# Ali_Main_Board.net
KiCad netlist of a schematic drawn in Altium Designer
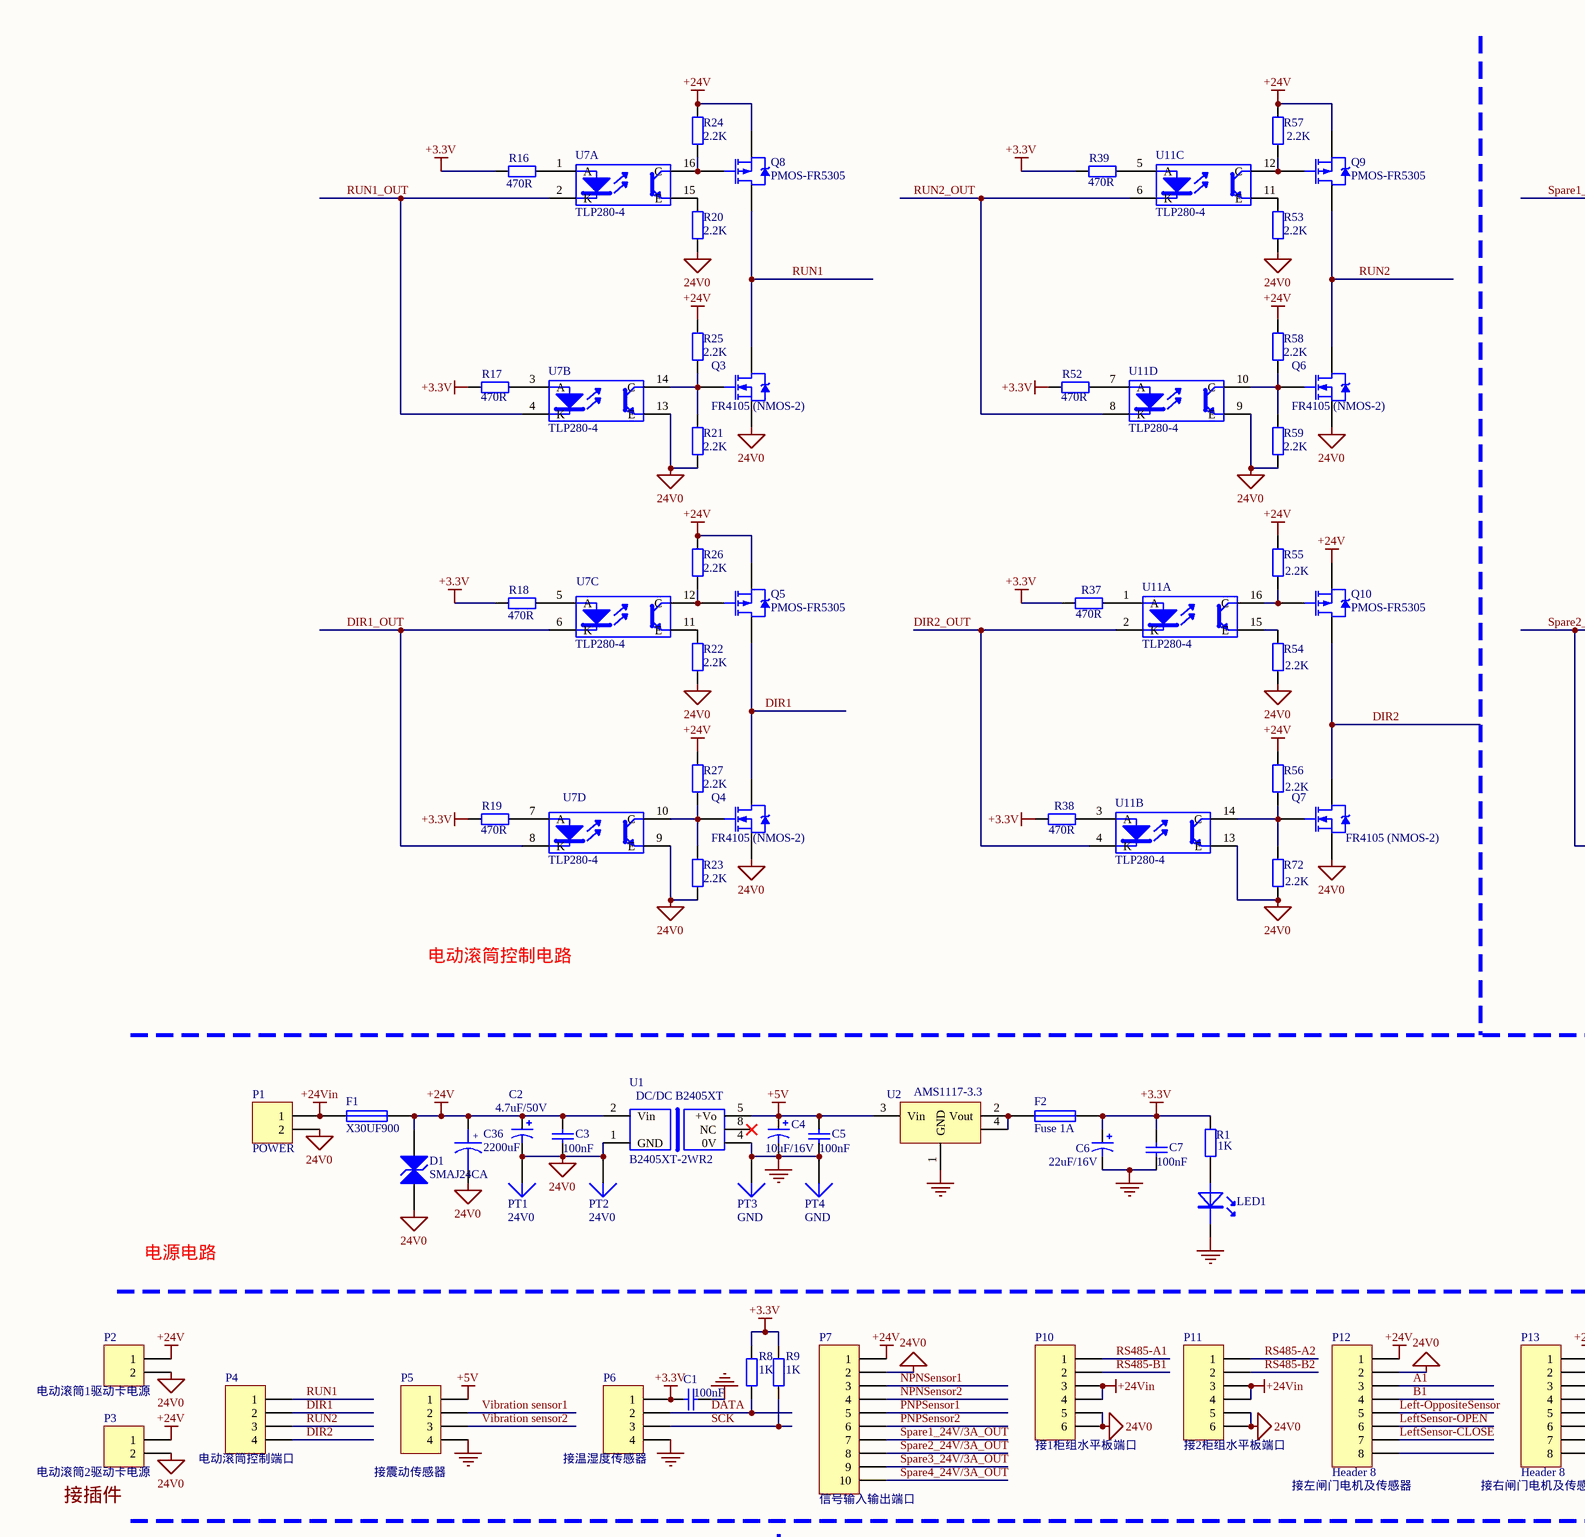
[diagram p0: Ali_Main_Board.SchDoc, top left]
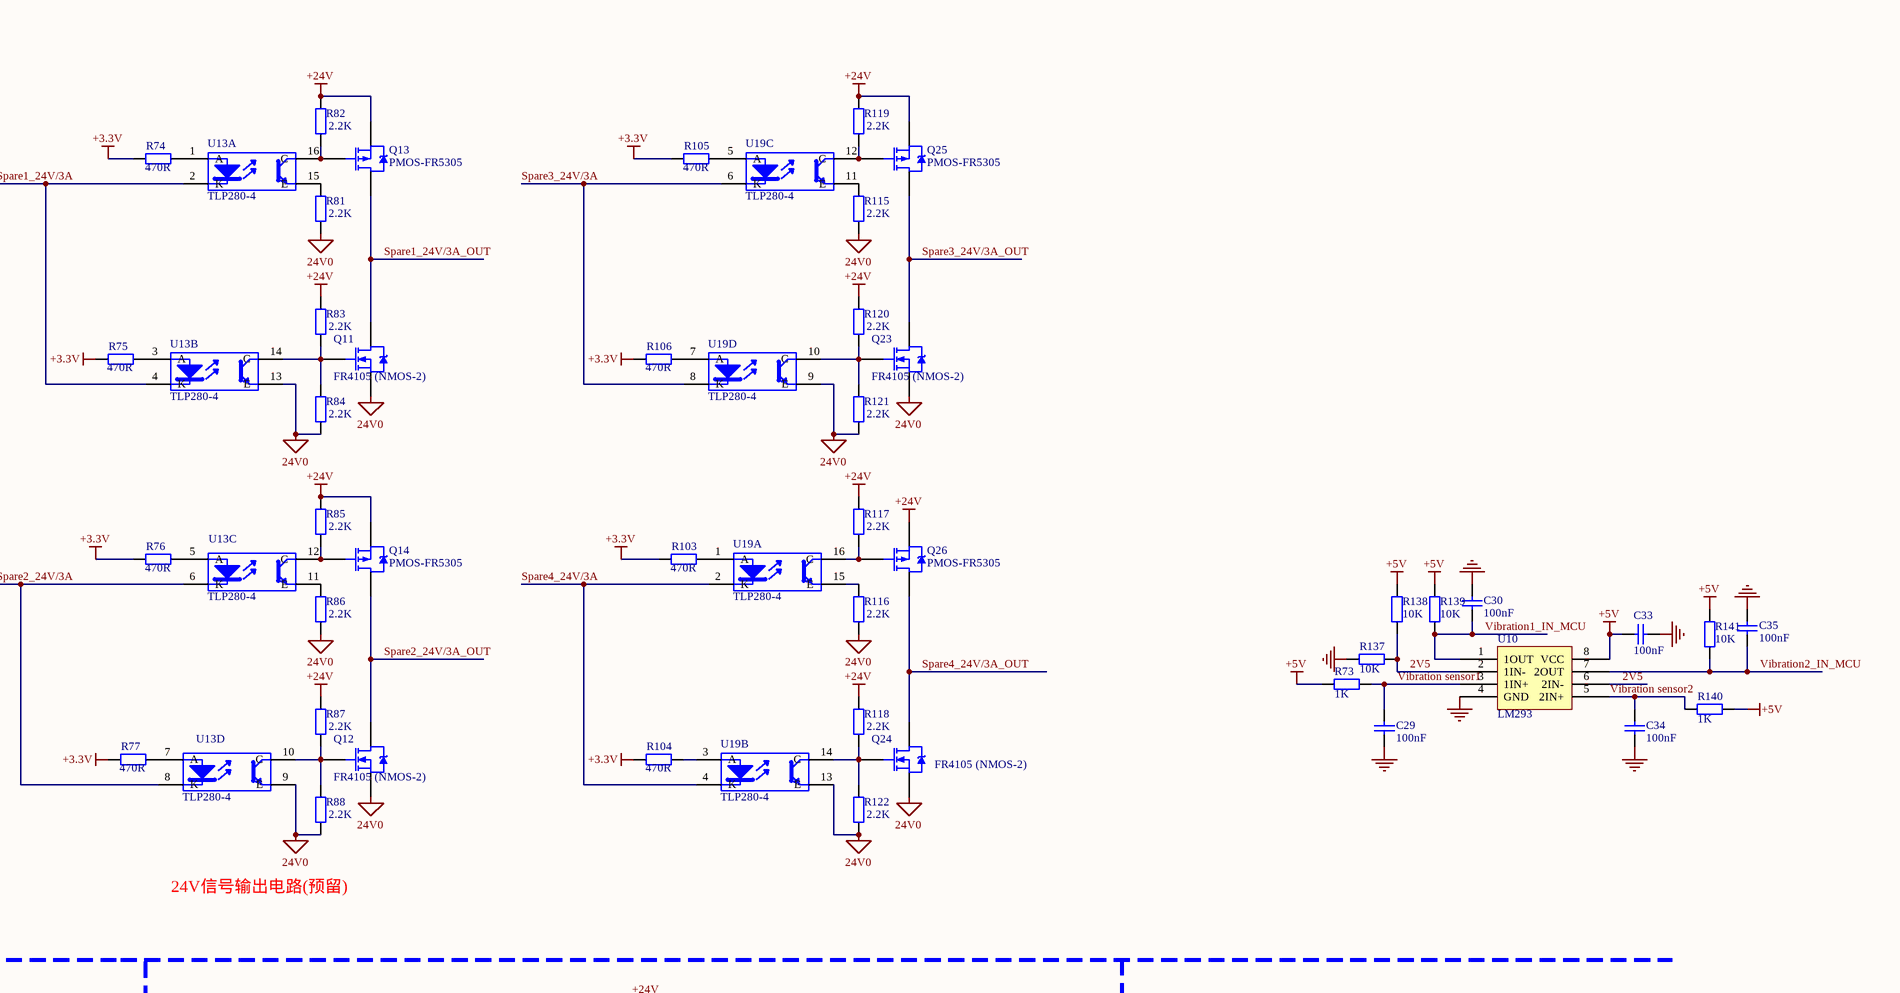
[diagram p1: Ali_Main_Board.SchDoc, top right]
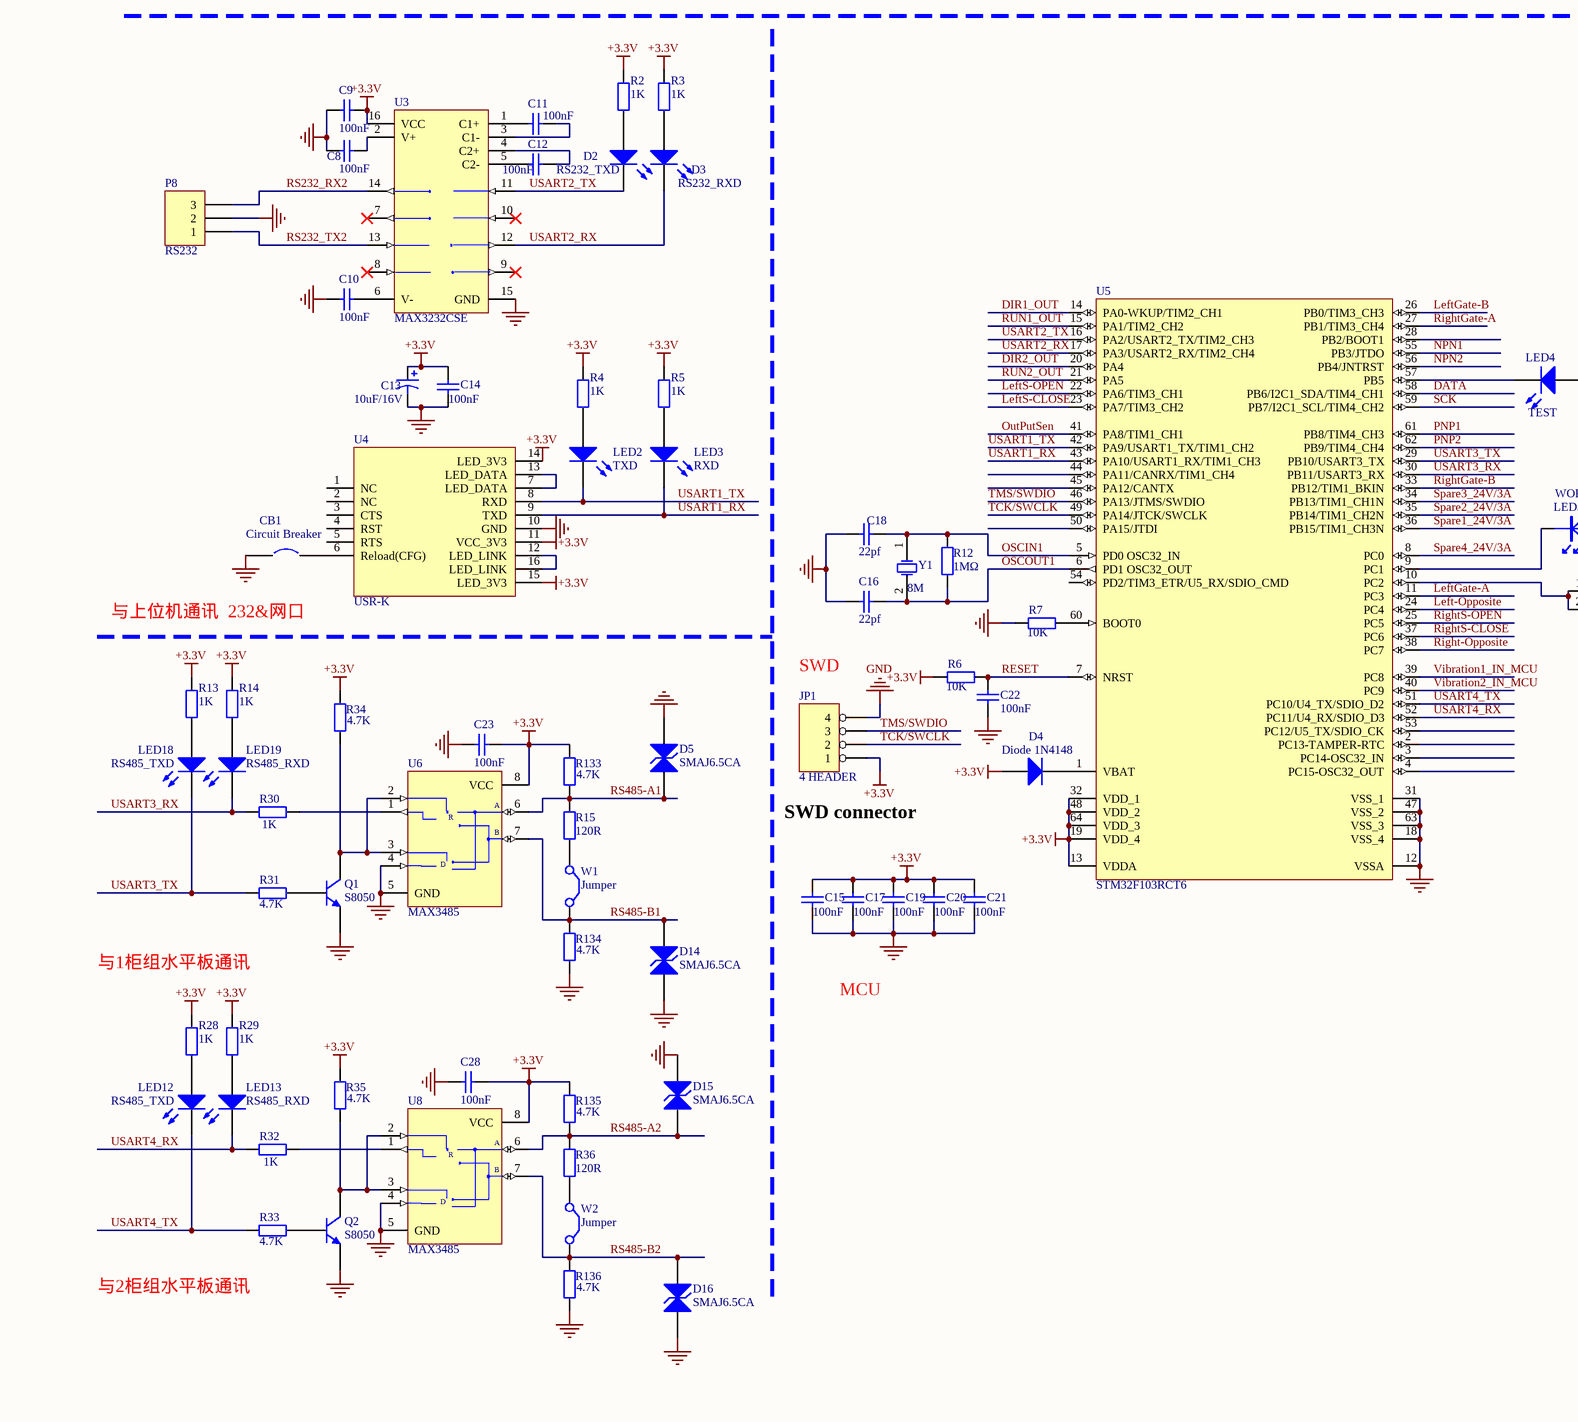
[diagram p2: Ali_Main_Board.SchDoc, bottom left]
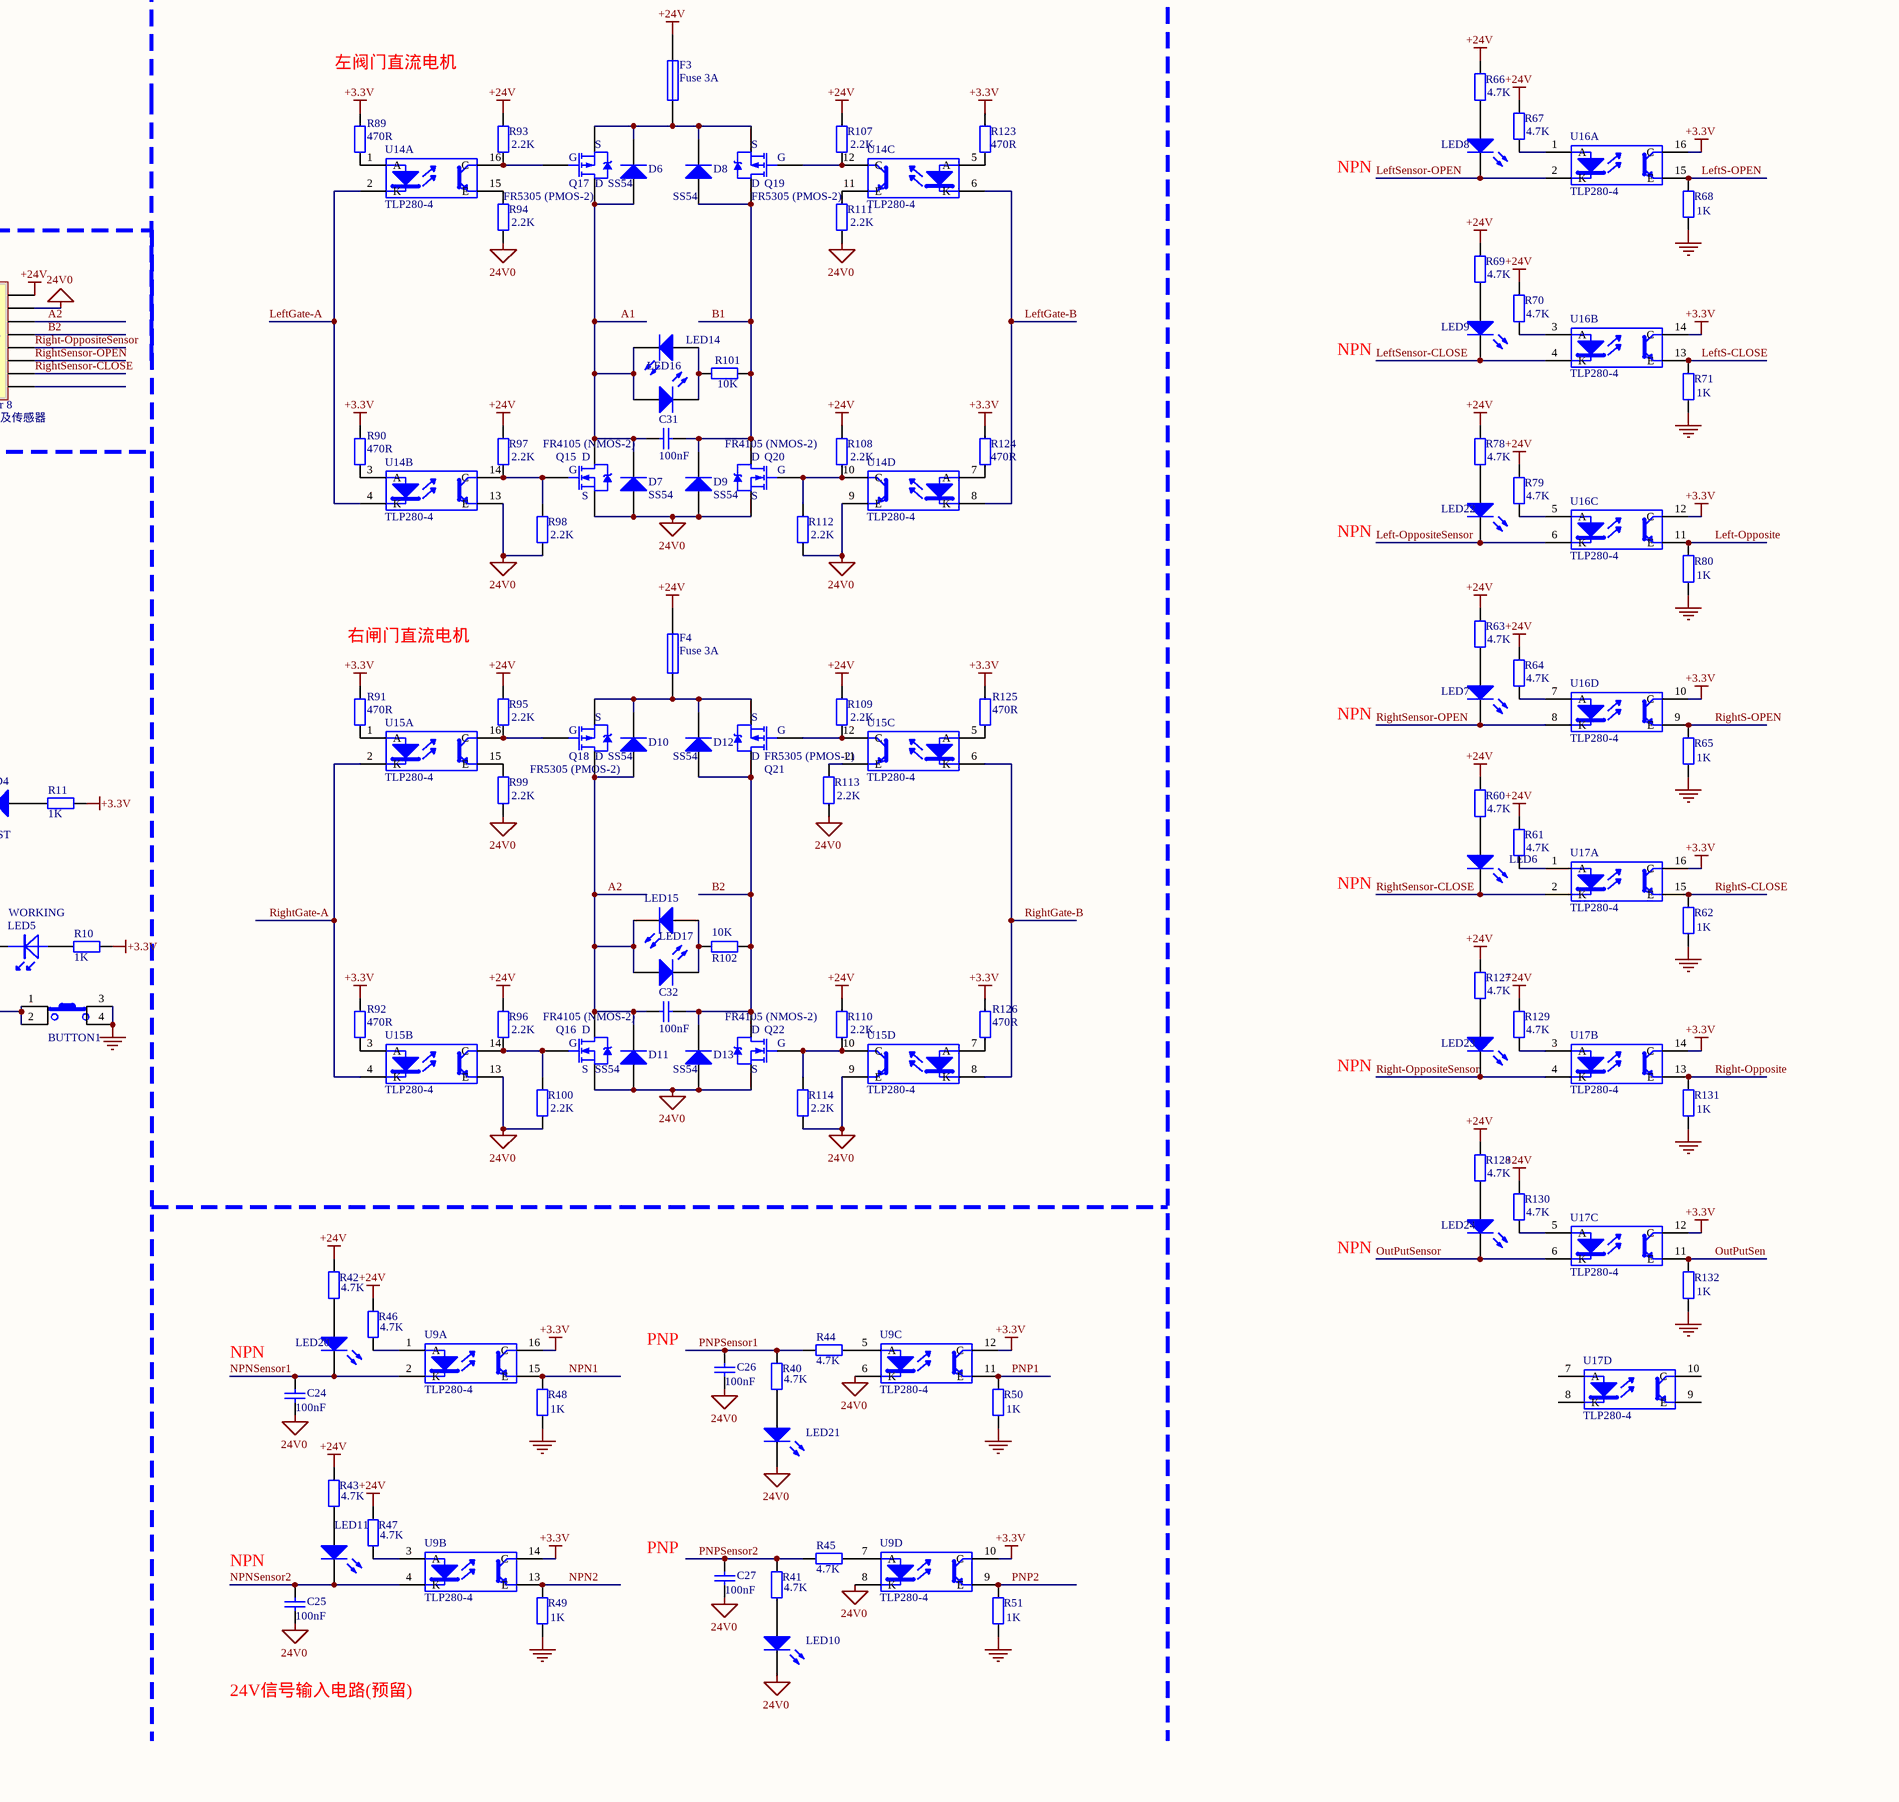
[diagram p3: Ali_Main_Board.SchDoc, bottom right]

(export (version "E")
  (design (tool "Eeschema 10.0.6"))
  (components
    (comp (ref "BUTTON1") (value "SW4") (footprint "BUTTON") (libsource (lib "原理图元件库") (part "SW4")))
    (comp (ref "C1")
      (value "100nF")
      (footprint "0805")
      (description "Capacitor")
      (fields (field (name "PUBLISHER") "Altium Limited"))
      (libsource (lib "Miscellaneous Devices") (part "Cap"))
    )
    (comp (ref "C2")
      (value "4.7uF/50V")
      (footprint "CAP D-7343")
      (description "Polarized Capacitor (Surface Mount)")
      (fields (field (name "Comment") "Cap Pol3") (field (name "PUBLISHER") "Altium Limited"))
      (libsource (lib "Miscellaneous Devices") (part "Cap Pol3"))
    )
    (comp (ref "C3")
      (value "100nF")
      (footprint "0805")
      (description "Capacitor")
      (fields (field (name "PUBLISHER") "Altium Limited"))
      (libsource (lib "Miscellaneous Devices") (part "Cap"))
    )
    (comp (ref "C4")
      (value "10uF/16V")
      (footprint "CAP A-3216")
      (description "Polarized Capacitor (Surface Mount)")
      (fields (field (name "Comment") "Cap Pol3") (field (name "PUBLISHER") "Altium Limited"))
      (libsource (lib "Miscellaneous Devices") (part "Cap Pol3"))
    )
    (comp (ref "C5")
      (value "100nF")
      (footprint "0805")
      (description "Capacitor")
      (fields (field (name "PUBLISHER") "Altium Limited"))
      (libsource (lib "Miscellaneous Devices") (part "Cap"))
    )
    (comp (ref "C6")
      (value "22uF/16V")
      (footprint "CAP D-7343")
      (description "Polarized Capacitor (Surface Mount)")
      (fields (field (name "Comment") "Cap Pol3") (field (name "PUBLISHER") "Altium Limited"))
      (libsource (lib "Miscellaneous Devices") (part "Cap Pol3"))
    )
    (comp (ref "C7")
      (value "100nF")
      (footprint "0805")
      (description "Capacitor")
      (fields (field (name "PUBLISHER") "Altium Limited"))
      (libsource (lib "Miscellaneous Devices") (part "Cap"))
    )
    (comp (ref "C8")
      (value "100nF")
      (footprint "0805")
      (description "Capacitor")
      (fields (field (name "PUBLISHER") "Altium Limited"))
      (libsource (lib "Miscellaneous Devices") (part "Cap"))
    )
    (comp (ref "C9")
      (value "100nF")
      (footprint "0805")
      (description "Capacitor")
      (fields (field (name "PUBLISHER") "Altium Limited"))
      (libsource (lib "Miscellaneous Devices") (part "Cap"))
    )
    (comp (ref "C10")
      (value "100nF")
      (footprint "0805")
      (description "Capacitor")
      (fields (field (name "PUBLISHER") "Altium Limited"))
      (libsource (lib "Miscellaneous Devices") (part "Cap"))
    )
    (comp (ref "C11")
      (value "100nF")
      (footprint "0805")
      (description "Capacitor")
      (fields (field (name "PUBLISHER") "Altium Limited"))
      (libsource (lib "Miscellaneous Devices") (part "Cap"))
    )
    (comp (ref "C12")
      (value "100nF")
      (footprint "0805")
      (description "Capacitor")
      (fields (field (name "PUBLISHER") "Altium Limited"))
      (libsource (lib "Miscellaneous Devices") (part "Cap"))
    )
    (comp (ref "C13")
      (value "10uF/16V")
      (footprint "CAP A-3216")
      (description "Polarized Capacitor (Surface Mount)")
      (fields (field (name "Comment") "Cap Pol3") (field (name "PUBLISHER") "Altium Limited"))
      (libsource (lib "Miscellaneous Devices") (part "Cap Pol3"))
    )
    (comp (ref "C14")
      (value "100nF")
      (footprint "0805")
      (description "Capacitor")
      (fields (field (name "PUBLISHER") "Altium Limited"))
      (libsource (lib "Miscellaneous Devices") (part "Cap"))
    )
    (comp (ref "C15")
      (value "100nF")
      (footprint "0805")
      (description "Capacitor")
      (fields (field (name "PUBLISHER") "Altium Limited"))
      (libsource (lib "Miscellaneous Devices") (part "Cap"))
    )
    (comp (ref "C16")
      (value "22pf")
      (footprint "0805")
      (description "Capacitor")
      (fields (field (name "PUBLISHER") "Altium Limited"))
      (libsource (lib "Miscellaneous Devices") (part "Cap"))
    )
    (comp (ref "C17")
      (value "100nF")
      (footprint "0805")
      (description "Capacitor")
      (fields (field (name "PUBLISHER") "Altium Limited"))
      (libsource (lib "Miscellaneous Devices") (part "Cap"))
    )
    (comp (ref "C18")
      (value "22pf")
      (footprint "0805")
      (description "Capacitor")
      (fields (field (name "PUBLISHER") "Altium Limited"))
      (libsource (lib "Miscellaneous Devices") (part "Cap"))
    )
    (comp (ref "C19")
      (value "100nF")
      (footprint "0805")
      (description "Capacitor")
      (fields (field (name "PUBLISHER") "Altium Limited"))
      (libsource (lib "Miscellaneous Devices") (part "Cap"))
    )
    (comp (ref "C20")
      (value "100nF")
      (footprint "0805")
      (description "Capacitor")
      (fields (field (name "PUBLISHER") "Altium Limited"))
      (libsource (lib "Miscellaneous Devices") (part "Cap"))
    )
    (comp (ref "C21")
      (value "100nF")
      (footprint "0805")
      (description "Capacitor")
      (fields (field (name "PUBLISHER") "Altium Limited"))
      (libsource (lib "Miscellaneous Devices") (part "Cap"))
    )
    (comp (ref "C22")
      (value "100nF")
      (footprint "0805")
      (description "Capacitor")
      (fields (field (name "Comment") "Cap") (field (name "PUBLISHER") "Altium Limited"))
      (libsource (lib "Miscellaneous Devices") (part "Cap"))
    )
    (comp (ref "C23")
      (value "100nF")
      (footprint "0805")
      (description "Capacitor")
      (fields (field (name "PUBLISHER") "Altium Limited"))
      (libsource (lib "Miscellaneous Devices") (part "Cap"))
    )
    (comp (ref "C24")
      (value "100nF")
      (footprint "0805")
      (description "Capacitor")
      (fields (field (name "Comment") "Cap") (field (name "PUBLISHER") "Altium Limited"))
      (libsource (lib "Miscellaneous Devices") (part "Cap"))
    )
    (comp (ref "C25")
      (value "100nF")
      (footprint "0805")
      (description "Capacitor")
      (fields (field (name "Comment") "Cap") (field (name "PUBLISHER") "Altium Limited"))
      (libsource (lib "Miscellaneous Devices") (part "Cap"))
    )
    (comp (ref "C26")
      (value "100nF")
      (footprint "0805")
      (description "Capacitor")
      (fields (field (name "Comment") "Cap") (field (name "PUBLISHER") "Altium Limited"))
      (libsource (lib "Miscellaneous Devices") (part "Cap"))
    )
    (comp (ref "C27")
      (value "100nF")
      (footprint "0805")
      (description "Capacitor")
      (fields (field (name "Comment") "Cap") (field (name "PUBLISHER") "Altium Limited"))
      (libsource (lib "Miscellaneous Devices") (part "Cap"))
    )
    (comp (ref "C28")
      (value "100nF")
      (footprint "0805")
      (description "Capacitor")
      (fields (field (name "PUBLISHER") "Altium Limited"))
      (libsource (lib "Miscellaneous Devices") (part "Cap"))
    )
    (comp (ref "C29")
      (value "100nF")
      (footprint "0805")
      (description "Capacitor")
      (fields (field (name "PUBLISHER") "Altium Limited"))
      (libsource (lib "Miscellaneous Devices") (part "Cap"))
    )
    (comp (ref "C30")
      (value "100nF")
      (footprint "0805")
      (description "Capacitor")
      (fields (field (name "PUBLISHER") "Altium Limited"))
      (libsource (lib "Miscellaneous Devices") (part "Cap"))
    )
    (comp (ref "C31")
      (value "100nF")
      (footprint "0805")
      (description "Capacitor")
      (fields (field (name "PUBLISHER") "Altium Limited"))
      (libsource (lib "Miscellaneous Devices") (part "Cap"))
    )
    (comp (ref "C32")
      (value "100nF")
      (footprint "0805")
      (description "Capacitor")
      (fields (field (name "PUBLISHER") "Altium Limited"))
      (libsource (lib "Miscellaneous Devices") (part "Cap"))
    )
    (comp (ref "C33")
      (value "100nF")
      (footprint "0805")
      (description "Capacitor")
      (fields (field (name "PUBLISHER") "Altium Limited"))
      (libsource (lib "Miscellaneous Devices") (part "Cap"))
    )
    (comp (ref "C34")
      (value "100nF")
      (footprint "0805")
      (description "Capacitor")
      (fields (field (name "PUBLISHER") "Altium Limited"))
      (libsource (lib "Miscellaneous Devices") (part "Cap"))
    )
    (comp (ref "C35")
      (value "100nF")
      (footprint "0805")
      (description "Capacitor")
      (fields (field (name "PUBLISHER") "Altium Limited"))
      (libsource (lib "Miscellaneous Devices") (part "Cap"))
    )
    (comp (ref "C36")
      (value "C_2200uF")
      (footprint "C7.8*17")
      (fields (field (name "ALTIUM_UNNAMED_1") "2200uF"))
      (libsource (lib "myIntegrated_Library1") (part "C_2200uF"))
    )
    (comp (ref "CB1")
      (value "Circuit Breaker")
      (footprint "HDR1X2")
      (fields (field (name "PUBLISHER") "Altium Limited"))
      (libsource (lib "Miscellaneous Devices") (part "Circuit Breaker"))
    )
    (comp (ref "D1")
      (value "SMAJ24CA")
      (footprint "SMB(DO-214AA)_S1")
      (description "TVS")
      (libsource (lib "Miscellaneous Devices LC") (part "SMB/DO-214AA P6SMB6.8CA"))
    )
    (comp (ref "D2")
      (value "RS232_TXD")
      (footprint "LED-0805")
      (description "Typical RED, GREEN, YELLOW, AMBER GaAs LED")
      (fields (field (name "PUBLISHER") "Altium Limited"))
      (libsource (lib "Miscellaneous Devices") (part "LED2"))
    )
    (comp (ref "D3")
      (value "RS232_RXD")
      (footprint "LED-0805")
      (description "Typical RED, GREEN, YELLOW, AMBER GaAs LED")
      (fields (field (name "PUBLISHER") "Altium Limited"))
      (libsource (lib "Miscellaneous Devices") (part "LED2"))
    )
    (comp (ref "D4")
      (value "Diode 1N4148")
      (footprint "LED-0805")
      (description "High Conductance Fast Diode")
      (fields (field (name "PUBLISHER") "Altium Limited"))
      (libsource (lib "Miscellaneous Devices") (part "Diode 1N4148"))
    )
    (comp (ref "D5")
      (value "SMAJ6.5CA")
      (footprint "SMA(DO-214AC)_S1")
      (description "TVS")
      (libsource (lib "Miscellaneous Devices LC") (part "SMB/DO-214AA P6SMB6.8CA"))
    )
    (comp (ref "D6")
      (value "SS54")
      (footprint "Footprint:SMA")
      (description "High Conductance Fast Diode")
      (fields (field (name "PUBLISHER") "Altium Limited"))
      (libsource (lib "Miscellaneous Devices") (part "Diode 1N4148"))
    )
    (comp (ref "D7")
      (value "SS54")
      (footprint "Footprint:SMA")
      (description "High Conductance Fast Diode")
      (fields (field (name "PUBLISHER") "Altium Limited"))
      (libsource (lib "Miscellaneous Devices") (part "Diode 1N4148"))
    )
    (comp (ref "D8")
      (value "SS54")
      (footprint "Footprint:SMA")
      (description "High Conductance Fast Diode")
      (fields (field (name "PUBLISHER") "Altium Limited"))
      (libsource (lib "Miscellaneous Devices") (part "Diode 1N4148"))
    )
    (comp (ref "D9")
      (value "SS54")
      (footprint "Footprint:SMA")
      (description "High Conductance Fast Diode")
      (fields (field (name "PUBLISHER") "Altium Limited"))
      (libsource (lib "Miscellaneous Devices") (part "Diode 1N4148"))
    )
    (comp (ref "D10")
      (value "SS54")
      (footprint "Footprint:SMA")
      (description "High Conductance Fast Diode")
      (fields (field (name "PUBLISHER") "Altium Limited"))
      (libsource (lib "Miscellaneous Devices") (part "Diode 1N4148"))
    )
    (comp (ref "D11")
      (value "SS54")
      (footprint "Footprint:SMA")
      (description "High Conductance Fast Diode")
      (fields (field (name "PUBLISHER") "Altium Limited"))
      (libsource (lib "Miscellaneous Devices") (part "Diode 1N4148"))
    )
    (comp (ref "D12")
      (value "SS54")
      (footprint "Footprint:SMA")
      (description "High Conductance Fast Diode")
      (fields (field (name "PUBLISHER") "Altium Limited"))
      (libsource (lib "Miscellaneous Devices") (part "Diode 1N4148"))
    )
    (comp (ref "D13")
      (value "SS54")
      (footprint "Footprint:SMA")
      (description "High Conductance Fast Diode")
      (fields (field (name "PUBLISHER") "Altium Limited"))
      (libsource (lib "Miscellaneous Devices") (part "Diode 1N4148"))
    )
    (comp (ref "D14")
      (value "SMAJ6.5CA")
      (footprint "SMA(DO-214AC)_S1")
      (description "TVS")
      (libsource (lib "Miscellaneous Devices LC") (part "SMB/DO-214AA P6SMB6.8CA"))
    )
    (comp (ref "D15")
      (value "SMAJ6.5CA")
      (footprint "SMA(DO-214AC)_S1")
      (description "TVS")
      (libsource (lib "Miscellaneous Devices LC") (part "SMB/DO-214AA P6SMB6.8CA"))
    )
    (comp (ref "D16")
      (value "SMAJ6.5CA")
      (footprint "SMA(DO-214AC)_S1")
      (description "TVS")
      (libsource (lib "Miscellaneous Devices LC") (part "SMB/DO-214AA P6SMB6.8CA"))
    )
    (comp (ref "F1")
      (value "X30UF900")
      (footprint "X30UF900")
      (description "Fuse")
      (fields (field (name "PUBLISHER") "Altium Limited"))
      (libsource (lib "Miscellaneous Devices") (part "Fuse 1"))
    )
    (comp (ref "F2")
      (value "Fuse 1A")
      (footprint "3225[1210]")
      (description "Fuse")
      (fields (field (name "PUBLISHER") "Altium Limited"))
      (libsource (lib "Miscellaneous Devices") (part "Fuse 1"))
    )
    (comp (ref "F3")
      (value "Fuse 3A")
      (footprint "3225[1210]")
      (description "Fuse")
      (fields (field (name "PUBLISHER") "Altium Limited"))
      (libsource (lib "Miscellaneous Devices") (part "Fuse 1"))
    )
    (comp (ref "F4")
      (value "Fuse 3A")
      (footprint "3225[1210]")
      (description "Fuse")
      (fields (field (name "PUBLISHER") "Altium Limited"))
      (libsource (lib "Miscellaneous Devices") (part "Fuse 1"))
    )
    (comp (ref "JP1")
      (value "4 HEADER")
      (footprint "CON4_1.5")
      (description "4 Pin Header")
      (libsource (lib "myIntegrated_Library1") (part "4 HEADER"))
    )
    (comp (ref "LED1") (value "LED") (footprint "LED-0805") (libsource (lib "*") (part "LED")))
    (comp (ref "LED2")
      (value "TXD")
      (footprint "LED-0805")
      (description "Typical RED, GREEN, YELLOW, AMBER GaAs LED")
      (fields (field (name "PUBLISHER") "Altium Limited"))
      (libsource (lib "Miscellaneous Devices") (part "LED2"))
    )
    (comp (ref "LED3")
      (value "RXD")
      (footprint "LED-0805")
      (description "Typical RED, GREEN, YELLOW, AMBER GaAs LED")
      (fields (field (name "PUBLISHER") "Altium Limited"))
      (libsource (lib "Miscellaneous Devices") (part "LED2"))
    )
    (comp (ref "LED4")
      (value "TEST")
      (footprint "LED-0805")
      (description "Typical RED, GREEN, YELLOW, AMBER GaAs LED")
      (fields (field (name "PUBLISHER") "Altium Limited"))
      (libsource (lib "Miscellaneous Devices") (part "LED2"))
    )
    (comp (ref "LED5") (value "WORKING") (footprint "LED-0805") (libsource (lib "*") (part "LED")))
    (comp (ref "LED6")
      (value "LED")
      (footprint "LED-0805")
      (description "Typical RED, GREEN, YELLOW, AMBER GaAs LED")
      (fields (field (name "PUBLISHER") "Altium Limited"))
      (libsource (lib "Miscellaneous Devices") (part "LED2"))
    )
    (comp (ref "LED7")
      (value "LED")
      (footprint "LED-0805")
      (description "Typical RED, GREEN, YELLOW, AMBER GaAs LED")
      (fields (field (name "PUBLISHER") "Altium Limited"))
      (libsource (lib "Miscellaneous Devices") (part "LED2"))
    )
    (comp (ref "LED8")
      (value "LED")
      (footprint "LED-0805")
      (description "Typical RED, GREEN, YELLOW, AMBER GaAs LED")
      (fields (field (name "PUBLISHER") "Altium Limited"))
      (libsource (lib "Miscellaneous Devices") (part "LED2"))
    )
    (comp (ref "LED9")
      (value "LED")
      (footprint "LED-0805")
      (description "Typical RED, GREEN, YELLOW, AMBER GaAs LED")
      (fields (field (name "PUBLISHER") "Altium Limited"))
      (libsource (lib "Miscellaneous Devices") (part "LED2"))
    )
    (comp (ref "LED10")
      (value "LED")
      (footprint "LED-0805")
      (description "Typical RED, GREEN, YELLOW, AMBER GaAs LED")
      (fields (field (name "PUBLISHER") "Altium Limited"))
      (libsource (lib "Miscellaneous Devices") (part "LED2"))
    )
    (comp (ref "LED11")
      (value "LED")
      (footprint "LED-0805")
      (description "Typical RED, GREEN, YELLOW, AMBER GaAs LED")
      (fields (field (name "PUBLISHER") "Altium Limited"))
      (libsource (lib "Miscellaneous Devices") (part "LED2"))
    )
    (comp (ref "LED12")
      (value "RS485_TXD")
      (footprint "LED-0805")
      (description "Typical RED, GREEN, YELLOW, AMBER GaAs LED")
      (fields (field (name "PUBLISHER") "Altium Limited"))
      (libsource (lib "Miscellaneous Devices") (part "LED2"))
    )
    (comp (ref "LED13")
      (value "RS485_RXD")
      (footprint "LED-0805")
      (description "Typical RED, GREEN, YELLOW, AMBER GaAs LED")
      (fields (field (name "PUBLISHER") "Altium Limited"))
      (libsource (lib "Miscellaneous Devices") (part "LED2"))
    )
    (comp (ref "LED14")
      (value "LED")
      (footprint "LED-0805")
      (description "Typical RED, GREEN, YELLOW, AMBER GaAs LED")
      (fields (field (name "PUBLISHER") "Altium Limited"))
      (libsource (lib "Miscellaneous Devices") (part "LED2"))
    )
    (comp (ref "LED15")
      (value "LED")
      (footprint "LED-0805")
      (description "Typical RED, GREEN, YELLOW, AMBER GaAs LED")
      (fields (field (name "PUBLISHER") "Altium Limited"))
      (libsource (lib "Miscellaneous Devices") (part "LED2"))
    )
    (comp (ref "LED16")
      (value "LED")
      (footprint "LED-0805")
      (description "Typical RED, GREEN, YELLOW, AMBER GaAs LED")
      (fields (field (name "PUBLISHER") "Altium Limited"))
      (libsource (lib "Miscellaneous Devices") (part "LED2"))
    )
    (comp (ref "LED17")
      (value "LED")
      (footprint "LED-0805")
      (description "Typical RED, GREEN, YELLOW, AMBER GaAs LED")
      (fields (field (name "PUBLISHER") "Altium Limited"))
      (libsource (lib "Miscellaneous Devices") (part "LED2"))
    )
    (comp (ref "LED18")
      (value "RS485_TXD")
      (footprint "LED-0805")
      (description "Typical RED, GREEN, YELLOW, AMBER GaAs LED")
      (fields (field (name "PUBLISHER") "Altium Limited"))
      (libsource (lib "Miscellaneous Devices") (part "LED2"))
    )
    (comp (ref "LED19")
      (value "RS485_RXD")
      (footprint "LED-0805")
      (description "Typical RED, GREEN, YELLOW, AMBER GaAs LED")
      (fields (field (name "PUBLISHER") "Altium Limited"))
      (libsource (lib "Miscellaneous Devices") (part "LED2"))
    )
    (comp (ref "LED20")
      (value "LED")
      (footprint "LED-0805")
      (description "Typical RED, GREEN, YELLOW, AMBER GaAs LED")
      (fields (field (name "PUBLISHER") "Altium Limited"))
      (libsource (lib "Miscellaneous Devices") (part "LED2"))
    )
    (comp (ref "LED21")
      (value "LED")
      (footprint "LED-0805")
      (description "Typical RED, GREEN, YELLOW, AMBER GaAs LED")
      (fields (field (name "PUBLISHER") "Altium Limited"))
      (libsource (lib "Miscellaneous Devices") (part "LED2"))
    )
    (comp (ref "LED22")
      (value "LED")
      (footprint "LED-0805")
      (description "Typical RED, GREEN, YELLOW, AMBER GaAs LED")
      (fields (field (name "PUBLISHER") "Altium Limited"))
      (libsource (lib "Miscellaneous Devices") (part "LED2"))
    )
    (comp (ref "LED23")
      (value "LED")
      (footprint "LED-0805")
      (description "Typical RED, GREEN, YELLOW, AMBER GaAs LED")
      (fields (field (name "PUBLISHER") "Altium Limited"))
      (libsource (lib "Miscellaneous Devices") (part "LED2"))
    )
    (comp (ref "LED24")
      (value "LED")
      (footprint "LED-0805")
      (description "Typical RED, GREEN, YELLOW, AMBER GaAs LED")
      (fields (field (name "PUBLISHER") "Altium Limited"))
      (libsource (lib "Miscellaneous Devices") (part "LED2"))
    )
    (comp (ref "P1")
      (value "POWER")
      (footprint "VH3.96  2PIN")
      (description "Header, 2-Pin")
      (fields (field (name "PUBLISHER") "Altium Limited"))
      (libsource (lib "Miscellaneous Connectors") (part "Header 2"))
    )
    (comp (ref "P2")
      (value "电动滚筒1驱动卡电源")
      (footprint "VH3.96  2PIN")
      (description "Header, 2-Pin")
      (fields (field (name "PUBLISHER") "Altium Limited"))
      (libsource (lib "Miscellaneous Connectors") (part "Header 2"))
    )
    (comp (ref "P3")
      (value "电动滚筒2驱动卡电源")
      (footprint "VH3.96  2PIN")
      (description "Header, 2-Pin")
      (fields (field (name "PUBLISHER") "Altium Limited"))
      (libsource (lib "Miscellaneous Connectors") (part "Header 2"))
    )
    (comp (ref "P4")
      (value "电动滚筒控制端口")
      (footprint "VH3.96  4PIN")
      (description "Header, 4-Pin")
      (fields (field (name "PUBLISHER") "Altium Limited"))
      (libsource (lib "Miscellaneous Connectors") (part "Header 4"))
    )
    (comp (ref "P5")
      (value "接震动传感器")
      (footprint "VH3.96  4PIN")
      (description "Header, 4-Pin")
      (fields (field (name "PUBLISHER") "Altium Limited"))
      (libsource (lib "Miscellaneous Connectors") (part "Header 4"))
    )
    (comp (ref "P6")
      (value "接温湿度传感器")
      (footprint "VH3.96  4PIN")
      (description "Header, 4-Pin")
      (fields (field (name "PUBLISHER") "Altium Limited"))
      (libsource (lib "Miscellaneous Connectors") (part "Header 4"))
    )
    (comp (ref "P7")
      (value "信号输入输出端口")
      (footprint "VH3.96  10PIN")
      (description "Header, 10-Pin")
      (fields (field (name "PUBLISHER") "Altium Limited"))
      (libsource (lib "Miscellaneous Connectors") (part "Header 10"))
    )
    (comp (ref "P8")
      (value "RS232")
      (footprint "VH3.96  3PIN")
      (description "Header, 3-Pin")
      (fields (field (name "PUBLISHER") "Altium Limited"))
      (libsource (lib "Miscellaneous Connectors") (part "Header 3"))
    )
    (comp (ref "P10")
      (value "接1柜组水平板端口")
      (footprint "VH3.96  6PIN")
      (description "Header, 6-Pin")
      (fields (field (name "PUBLISHER") "Altium Limited"))
      (libsource (lib "Miscellaneous Connectors") (part "Header 6"))
    )
    (comp (ref "P11")
      (value "接2柜组水平板端口")
      (footprint "VH3.96  6PIN")
      (description "Header, 6-Pin")
      (fields (field (name "PUBLISHER") "Altium Limited"))
      (libsource (lib "Miscellaneous Connectors") (part "Header 6"))
    )
    (comp (ref "P12")
      (value "Header 8")
      (footprint "VH3.96  8PIN")
      (description "Header, 8-Pin")
      (fields (field (name "PUBLISHER") "Altium Limited"))
      (libsource (lib "Miscellaneous Connectors") (part "Header 8"))
    )
    (comp (ref "P13")
      (value "Header 8")
      (footprint "VH3.96  8PIN")
      (description "Header, 8-Pin")
      (fields (field (name "PUBLISHER") "Altium Limited"))
      (libsource (lib "Miscellaneous Connectors") (part "Header 8"))
    )
    (comp (ref "PT1")
      (value "24V0")
      (footprint "PLUG")
      (description "Plug")
      (fields (field (name "PUBLISHER") "Altium Limited"))
      (libsource (lib "Miscellaneous Connectors") (part "Plug"))
    )
    (comp (ref "PT2")
      (value "24V0")
      (footprint "PLUG")
      (description "Plug")
      (fields (field (name "PUBLISHER") "Altium Limited"))
      (libsource (lib "Miscellaneous Connectors") (part "Plug"))
    )
    (comp (ref "PT3")
      (value "GND")
      (footprint "PLUG")
      (description "Plug")
      (fields (field (name "PUBLISHER") "Altium Limited"))
      (libsource (lib "Miscellaneous Connectors") (part "Plug"))
    )
    (comp (ref "PT4")
      (value "GND")
      (footprint "PLUG")
      (description "Plug")
      (fields (field (name "PUBLISHER") "Altium Limited"))
      (libsource (lib "Miscellaneous Connectors") (part "Plug"))
    )
    (comp (ref "Q1")
      (value "S8050")
      (footprint "SOT-23(SOT-23-3)")
      (description "三极管")
      (libsource (lib "Miscellaneous Devices LC") (part "SOT-23 SS8050 Y1"))
    )
    (comp (ref "Q2")
      (value "S8050")
      (footprint "SOT-23(SOT-23-3)")
      (description "三极管")
      (libsource (lib "Miscellaneous Devices LC") (part "SOT-23 SS8050 Y1"))
    )
    (comp (ref "Q3")
      (value "FR4105 (NMOS-2)")
      (footprint "TO-252")
      (description "N-Channel Power MOSFET")
      (fields (field (name "PUBLISHER") "Altium Limited"))
      (libsource (lib "Miscellaneous Devices") (part "NMOS-2"))
    )
    (comp (ref "Q4")
      (value "FR4105 (NMOS-2)")
      (footprint "TO-252")
      (description "N-Channel Power MOSFET")
      (fields (field (name "PUBLISHER") "Altium Limited"))
      (libsource (lib "Miscellaneous Devices") (part "NMOS-2"))
    )
    (comp (ref "Q5")
      (value "PMOS-FR5305")
      (footprint "TO-252")
      (description "P-Channel Power MOSFET")
      (fields (field (name "PUBLISHER") "Altium Limited"))
      (libsource (lib "Miscellaneous Devices") (part "PMOS-2"))
    )
    (comp (ref "Q6")
      (value "FR4105 (NMOS-2)")
      (footprint "TO-252")
      (description "N-Channel Power MOSFET")
      (fields (field (name "PUBLISHER") "Altium Limited"))
      (libsource (lib "Miscellaneous Devices") (part "NMOS-2"))
    )
    (comp (ref "Q7")
      (value "FR4105 (NMOS-2)")
      (footprint "TO-252")
      (description "N-Channel Power MOSFET")
      (fields (field (name "PUBLISHER") "Altium Limited"))
      (libsource (lib "Miscellaneous Devices") (part "NMOS-2"))
    )
    (comp (ref "Q8")
      (value "PMOS-FR5305")
      (footprint "TO-252")
      (description "P-Channel Power MOSFET")
      (fields (field (name "PUBLISHER") "Altium Limited"))
      (libsource (lib "Miscellaneous Devices") (part "PMOS-2"))
    )
    (comp (ref "Q9")
      (value "PMOS-FR5305")
      (footprint "TO-252")
      (description "P-Channel Power MOSFET")
      (fields (field (name "PUBLISHER") "Altium Limited"))
      (libsource (lib "Miscellaneous Devices") (part "PMOS-2"))
    )
    (comp (ref "Q10")
      (value "PMOS-FR5305")
      (footprint "TO-252")
      (description "P-Channel Power MOSFET")
      (fields (field (name "PUBLISHER") "Altium Limited"))
      (libsource (lib "Miscellaneous Devices") (part "PMOS-2"))
    )
    (comp (ref "Q11")
      (value "FR4105 (NMOS-2)")
      (footprint "TO-252")
      (description "N-Channel Power MOSFET")
      (fields (field (name "PUBLISHER") "Altium Limited"))
      (libsource (lib "Miscellaneous Devices") (part "NMOS-2"))
    )
    (comp (ref "Q12")
      (value "FR4105 (NMOS-2)")
      (footprint "TO-252")
      (description "N-Channel Power MOSFET")
      (fields (field (name "PUBLISHER") "Altium Limited"))
      (libsource (lib "Miscellaneous Devices") (part "NMOS-2"))
    )
    (comp (ref "Q13")
      (value "PMOS-FR5305")
      (footprint "TO-252")
      (description "P-Channel Power MOSFET")
      (fields (field (name "PUBLISHER") "Altium Limited"))
      (libsource (lib "Miscellaneous Devices") (part "PMOS-2"))
    )
    (comp (ref "Q14")
      (value "PMOS-FR5305")
      (footprint "TO-252")
      (description "P-Channel Power MOSFET")
      (fields (field (name "PUBLISHER") "Altium Limited"))
      (libsource (lib "Miscellaneous Devices") (part "PMOS-2"))
    )
    (comp (ref "Q15")
      (value "FR4105 (NMOS-2)")
      (footprint "TO-252")
      (description "N-Channel Power MOSFET")
      (fields (field (name "PUBLISHER") "Altium Limited"))
      (libsource (lib "Miscellaneous Devices") (part "NMOS-2"))
    )
    (comp (ref "Q16")
      (value "FR4105 (NMOS-2)")
      (footprint "TO-252")
      (description "N-Channel Power MOSFET")
      (fields (field (name "PUBLISHER") "Altium Limited"))
      (libsource (lib "Miscellaneous Devices") (part "NMOS-2"))
    )
    (comp (ref "Q17")
      (value "FR5305 (PMOS-2)")
      (footprint "TO-252")
      (description "P-Channel Power MOSFET")
      (fields (field (name "PUBLISHER") "Altium Limited"))
      (libsource (lib "Miscellaneous Devices") (part "PMOS-2"))
    )
    (comp (ref "Q18")
      (value "FR5305 (PMOS-2)")
      (footprint "TO-252")
      (description "P-Channel Power MOSFET")
      (fields (field (name "PUBLISHER") "Altium Limited"))
      (libsource (lib "Miscellaneous Devices") (part "PMOS-2"))
    )
    (comp (ref "Q19")
      (value "FR5305 (PMOS-2)")
      (footprint "TO-252")
      (description "P-Channel Power MOSFET")
      (fields (field (name "PUBLISHER") "Altium Limited"))
      (libsource (lib "Miscellaneous Devices") (part "PMOS-2"))
    )
    (comp (ref "Q20")
      (value "FR4105 (NMOS-2)")
      (footprint "TO-252")
      (description "N-Channel Power MOSFET")
      (fields (field (name "PUBLISHER") "Altium Limited"))
      (libsource (lib "Miscellaneous Devices") (part "NMOS-2"))
    )
    (comp (ref "Q21")
      (value "FR5305 (PMOS-2)")
      (footprint "TO-252")
      (description "P-Channel Power MOSFET")
      (fields (field (name "PUBLISHER") "Altium Limited"))
      (libsource (lib "Miscellaneous Devices") (part "PMOS-2"))
    )
    (comp (ref "Q22")
      (value "FR4105 (NMOS-2)")
      (footprint "TO-252")
      (description "N-Channel Power MOSFET")
      (fields (field (name "PUBLISHER") "Altium Limited"))
      (libsource (lib "Miscellaneous Devices") (part "NMOS-2"))
    )
    (comp (ref "Q23")
      (value "FR4105 (NMOS-2)")
      (footprint "TO-252")
      (description "N-Channel Power MOSFET")
      (fields (field (name "PUBLISHER") "Altium Limited"))
      (libsource (lib "Miscellaneous Devices") (part "NMOS-2"))
    )
    (comp (ref "Q24")
      (value "FR4105 (NMOS-2)")
      (footprint "TO-252")
      (description "N-Channel Power MOSFET")
      (fields (field (name "PUBLISHER") "Altium Limited"))
      (libsource (lib "Miscellaneous Devices") (part "NMOS-2"))
    )
    (comp (ref "Q25")
      (value "PMOS-FR5305")
      (footprint "TO-252")
      (description "P-Channel Power MOSFET")
      (fields (field (name "PUBLISHER") "Altium Limited"))
      (libsource (lib "Miscellaneous Devices") (part "PMOS-2"))
    )
    (comp (ref "Q26")
      (value "PMOS-FR5305")
      (footprint "TO-252")
      (description "P-Channel Power MOSFET")
      (fields (field (name "PUBLISHER") "Altium Limited"))
      (libsource (lib "Miscellaneous Devices") (part "PMOS-2"))
    )
    (comp (ref "R1")
      (value "1K")
      (footprint "0805")
      (description "Resistor")
      (fields (field (name "PUBLISHER") "Altium Limited"))
      (libsource (lib "") (part "Res2_3"))
    )
    (comp (ref "R2")
      (value "1K")
      (footprint "0805")
      (description "Resistor")
      (fields (field (name "PUBLISHER") "Altium Limited"))
      (libsource (lib "") (part "Res2_3"))
    )
    (comp (ref "R3")
      (value "1K")
      (footprint "0805")
      (description "Resistor")
      (fields (field (name "PUBLISHER") "Altium Limited"))
      (libsource (lib "") (part "Res2_3"))
    )
    (comp (ref "R4")
      (value "1K")
      (footprint "0805")
      (description "Resistor")
      (fields (field (name "PUBLISHER") "Altium Limited"))
      (libsource (lib "") (part "Res2_3"))
    )
    (comp (ref "R5")
      (value "1K")
      (footprint "0805")
      (description "Resistor")
      (fields (field (name "PUBLISHER") "Altium Limited"))
      (libsource (lib "") (part "Res2_3"))
    )
    (comp (ref "R6")
      (value "10K")
      (footprint "0805")
      (description "Resistor")
      (fields (field (name "PUBLISHER") "Altium Limited"))
      (libsource (lib "") (part "Res2_2"))
    )
    (comp (ref "R7")
      (value "10K")
      (footprint "0805")
      (description "Resistor")
      (fields (field (name "PUBLISHER") "Altium Limited"))
      (libsource (lib "") (part "Res2_2"))
    )
    (comp (ref "R8")
      (value "1K")
      (footprint "0805")
      (description "Resistor")
      (fields (field (name "PUBLISHER") "Altium Limited"))
      (libsource (lib "") (part "Res2_3"))
    )
    (comp (ref "R9")
      (value "1K")
      (footprint "0805")
      (description "Resistor")
      (fields (field (name "PUBLISHER") "Altium Limited"))
      (libsource (lib "") (part "Res2_3"))
    )
    (comp (ref "R10")
      (value "1K")
      (footprint "0805")
      (description "Resistor")
      (fields (field (name "PUBLISHER") "Altium Limited"))
      (libsource (lib "Miscellaneous Devices") (part "Res2"))
    )
    (comp (ref "R11")
      (value "1K")
      (footprint "0805")
      (description "Resistor")
      (fields (field (name "PUBLISHER") "Altium Limited"))
      (libsource (lib "Miscellaneous Devices") (part "Res2"))
    )
    (comp (ref "R12")
      (value "1MΩ")
      (footprint "0805")
      (description "Resistor")
      (fields (field (name "PUBLISHER") "Altium Limited"))
      (libsource (lib "") (part "Res2_1"))
    )
    (comp (ref "R13")
      (value "1K")
      (footprint "0805")
      (description "Resistor")
      (fields (field (name "PUBLISHER") "Altium Limited"))
      (libsource (lib "") (part "Res2_3"))
    )
    (comp (ref "R14")
      (value "1K")
      (footprint "0805")
      (description "Resistor")
      (fields (field (name "PUBLISHER") "Altium Limited"))
      (libsource (lib "") (part "Res2_3"))
    )
    (comp (ref "R15")
      (value "120R")
      (footprint "0805")
      (description "Resistor")
      (fields (field (name "PUBLISHER") "Altium Limited"))
      (libsource (lib "") (part "Res2_1"))
    )
    (comp (ref "R16")
      (value "470R")
      (footprint "0805")
      (description "Resistor")
      (fields (field (name "PUBLISHER") "Altium Limited"))
      (libsource (lib "Miscellaneous Devices") (part "Res2"))
    )
    (comp (ref "R17")
      (value "470R")
      (footprint "0805")
      (description "Resistor")
      (fields (field (name "PUBLISHER") "Altium Limited"))
      (libsource (lib "") (part "Res2_2"))
    )
    (comp (ref "R18")
      (value "470R")
      (footprint "0805")
      (description "Resistor")
      (fields (field (name "PUBLISHER") "Altium Limited"))
      (libsource (lib "") (part "Res2_2"))
    )
    (comp (ref "R19")
      (value "470R")
      (footprint "0805")
      (description "Resistor")
      (fields (field (name "PUBLISHER") "Altium Limited"))
      (libsource (lib "") (part "Res2_2"))
    )
    (comp (ref "R20")
      (value "2.2K")
      (footprint "0805")
      (description "Resistor")
      (fields (field (name "PUBLISHER") "Altium Limited"))
      (libsource (lib "") (part "Res2_1"))
    )
    (comp (ref "R21")
      (value "2.2K")
      (footprint "0805")
      (description "Resistor")
      (fields (field (name "PUBLISHER") "Altium Limited"))
      (libsource (lib "") (part "Res2_1"))
    )
    (comp (ref "R22")
      (value "2.2K")
      (footprint "0805")
      (description "Resistor")
      (fields (field (name "PUBLISHER") "Altium Limited"))
      (libsource (lib "") (part "Res2_1"))
    )
    (comp (ref "R23")
      (value "2.2K")
      (footprint "0805")
      (description "Resistor")
      (fields (field (name "PUBLISHER") "Altium Limited"))
      (libsource (lib "") (part "Res2_1"))
    )
    (comp (ref "R24")
      (value "2.2K")
      (footprint "0805")
      (description "Resistor")
      (fields (field (name "PUBLISHER") "Altium Limited"))
      (libsource (lib "") (part "Res2_1"))
    )
    (comp (ref "R25")
      (value "2.2K")
      (footprint "0805")
      (description "Resistor")
      (fields (field (name "PUBLISHER") "Altium Limited"))
      (libsource (lib "") (part "Res2_1"))
    )
    (comp (ref "R26")
      (value "2.2K")
      (footprint "0805")
      (description "Resistor")
      (fields (field (name "PUBLISHER") "Altium Limited"))
      (libsource (lib "") (part "Res2_1"))
    )
    (comp (ref "R27")
      (value "2.2K")
      (footprint "0805")
      (description "Resistor")
      (fields (field (name "PUBLISHER") "Altium Limited"))
      (libsource (lib "") (part "Res2_1"))
    )
    (comp (ref "R28")
      (value "1K")
      (footprint "0805")
      (description "Resistor")
      (fields (field (name "PUBLISHER") "Altium Limited"))
      (libsource (lib "") (part "Res2_3"))
    )
    (comp (ref "R29")
      (value "1K")
      (footprint "0805")
      (description "Resistor")
      (fields (field (name "PUBLISHER") "Altium Limited"))
      (libsource (lib "") (part "Res2_3"))
    )
    (comp (ref "R30")
      (value "1K")
      (footprint "0805")
      (description "Resistor")
      (fields (field (name "PUBLISHER") "Altium Limited"))
      (libsource (lib "") (part "Res2_3"))
    )
    (comp (ref "R31")
      (value "4.7K")
      (footprint "0805")
      (description "Resistor")
      (fields (field (name "PUBLISHER") "Altium Limited"))
      (libsource (lib "") (part "Res2_2"))
    )
    (comp (ref "R32")
      (value "1K")
      (footprint "0805")
      (description "Resistor")
      (fields (field (name "PUBLISHER") "Altium Limited"))
      (libsource (lib "") (part "Res2_3"))
    )
    (comp (ref "R33")
      (value "4.7K")
      (footprint "0805")
      (description "Resistor")
      (fields (field (name "PUBLISHER") "Altium Limited"))
      (libsource (lib "") (part "Res2_2"))
    )
    (comp (ref "R34")
      (value "4.7K")
      (footprint "0805")
      (description "Resistor")
      (fields (field (name "PUBLISHER") "Altium Limited"))
      (libsource (lib "") (part "Res2_3"))
    )
    (comp (ref "R35")
      (value "4.7K")
      (footprint "0805")
      (description "Resistor")
      (fields (field (name "PUBLISHER") "Altium Limited"))
      (libsource (lib "") (part "Res2_3"))
    )
    (comp (ref "R36")
      (value "120R")
      (footprint "0805")
      (description "Resistor")
      (fields (field (name "PUBLISHER") "Altium Limited"))
      (libsource (lib "") (part "Res2_1"))
    )
    (comp (ref "R37")
      (value "470R")
      (footprint "0805")
      (description "Resistor")
      (fields (field (name "PUBLISHER") "Altium Limited"))
      (libsource (lib "") (part "Res2_2"))
    )
    (comp (ref "R38")
      (value "470R")
      (footprint "0805")
      (description "Resistor")
      (fields (field (name "PUBLISHER") "Altium Limited"))
      (libsource (lib "") (part "Res2_2"))
    )
    (comp (ref "R39")
      (value "470R")
      (footprint "0805")
      (description "Resistor")
      (fields (field (name "PUBLISHER") "Altium Limited"))
      (libsource (lib "Miscellaneous Devices") (part "Res2"))
    )
    (comp (ref "R40")
      (value "4.7K")
      (footprint "0805")
      (description "Resistor")
      (fields (field (name "PUBLISHER") "Altium Limited"))
      (libsource (lib "") (part "Res2_3"))
    )
    (comp (ref "R41")
      (value "4.7K")
      (footprint "0805")
      (description "Resistor")
      (fields (field (name "PUBLISHER") "Altium Limited"))
      (libsource (lib "") (part "Res2_3"))
    )
    (comp (ref "R42")
      (value "4.7K")
      (footprint "0805")
      (description "Resistor")
      (fields (field (name "PUBLISHER") "Altium Limited"))
      (libsource (lib "") (part "Res2_3"))
    )
    (comp (ref "R43")
      (value "4.7K")
      (footprint "0805")
      (description "Resistor")
      (fields (field (name "PUBLISHER") "Altium Limited"))
      (libsource (lib "") (part "Res2_3"))
    )
    (comp (ref "R44")
      (value "4.7K")
      (footprint "0805")
      (description "Resistor")
      (fields (field (name "PUBLISHER") "Altium Limited"))
      (libsource (lib "") (part "Res2_2"))
    )
    (comp (ref "R45")
      (value "4.7K")
      (footprint "0805")
      (description "Resistor")
      (fields (field (name "PUBLISHER") "Altium Limited"))
      (libsource (lib "") (part "Res2_2"))
    )
    (comp (ref "R46")
      (value "4.7K")
      (footprint "0805")
      (description "Resistor")
      (fields (field (name "PUBLISHER") "Altium Limited"))
      (libsource (lib "") (part "Res2_3"))
    )
    (comp (ref "R47")
      (value "4.7K")
      (footprint "0805")
      (description "Resistor")
      (fields (field (name "PUBLISHER") "Altium Limited"))
      (libsource (lib "") (part "Res2_3"))
    )
    (comp (ref "R48")
      (value "1K")
      (footprint "0805")
      (description "Resistor")
      (fields (field (name "PUBLISHER") "Altium Limited"))
      (libsource (lib "") (part "Res2_1"))
    )
    (comp (ref "R49")
      (value "1K")
      (footprint "0805")
      (description "Resistor")
      (fields (field (name "PUBLISHER") "Altium Limited"))
      (libsource (lib "") (part "Res2_1"))
    )
    (comp (ref "R50")
      (value "1K")
      (footprint "0805")
      (description "Resistor")
      (fields (field (name "PUBLISHER") "Altium Limited"))
      (libsource (lib "") (part "Res2_1"))
    )
    (comp (ref "R51")
      (value "1K")
      (footprint "0805")
      (description "Resistor")
      (fields (field (name "PUBLISHER") "Altium Limited"))
      (libsource (lib "") (part "Res2_1"))
    )
    (comp (ref "R52")
      (value "470R")
      (footprint "0805")
      (description "Resistor")
      (fields (field (name "PUBLISHER") "Altium Limited"))
      (libsource (lib "") (part "Res2_2"))
    )
    (comp (ref "R53")
      (value "2.2K")
      (footprint "0805")
      (description "Resistor")
      (fields (field (name "PUBLISHER") "Altium Limited"))
      (libsource (lib "") (part "Res2_1"))
    )
    (comp (ref "R54")
      (value "2.2K")
      (footprint "0805")
      (description "Resistor")
      (fields (field (name "PUBLISHER") "Altium Limited"))
      (libsource (lib "") (part "Res2_1"))
    )
    (comp (ref "R55")
      (value "2.2K")
      (footprint "0805")
      (description "Resistor")
      (fields (field (name "PUBLISHER") "Altium Limited"))
      (libsource (lib "") (part "Res2_1"))
    )
    (comp (ref "R56")
      (value "2.2K")
      (footprint "0805")
      (description "Resistor")
      (fields (field (name "PUBLISHER") "Altium Limited"))
      (libsource (lib "") (part "Res2_1"))
    )
    (comp (ref "R57")
      (value "2.2K")
      (footprint "0805")
      (description "Resistor")
      (fields (field (name "PUBLISHER") "Altium Limited"))
      (libsource (lib "") (part "Res2_1"))
    )
    (comp (ref "R58")
      (value "2.2K")
      (footprint "0805")
      (description "Resistor")
      (fields (field (name "PUBLISHER") "Altium Limited"))
      (libsource (lib "") (part "Res2_1"))
    )
    (comp (ref "R59")
      (value "2.2K")
      (footprint "0805")
      (description "Resistor")
      (fields (field (name "PUBLISHER") "Altium Limited"))
      (libsource (lib "") (part "Res2_1"))
    )
    (comp (ref "R60")
      (value "4.7K")
      (footprint "0805")
      (description "Resistor")
      (fields (field (name "PUBLISHER") "Altium Limited"))
      (libsource (lib "") (part "Res2_3"))
    )
    (comp (ref "R61")
      (value "4.7K")
      (footprint "0805")
      (description "Resistor")
      (fields (field (name "PUBLISHER") "Altium Limited"))
      (libsource (lib "") (part "Res2_3"))
    )
    (comp (ref "R62")
      (value "1K")
      (footprint "0805")
      (description "Resistor")
      (fields (field (name "PUBLISHER") "Altium Limited"))
      (libsource (lib "") (part "Res2_1"))
    )
    (comp (ref "R63")
      (value "4.7K")
      (footprint "0805")
      (description "Resistor")
      (fields (field (name "PUBLISHER") "Altium Limited"))
      (libsource (lib "") (part "Res2_3"))
    )
    (comp (ref "R64")
      (value "4.7K")
      (footprint "0805")
      (description "Resistor")
      (fields (field (name "PUBLISHER") "Altium Limited"))
      (libsource (lib "") (part "Res2_3"))
    )
    (comp (ref "R65")
      (value "1K")
      (footprint "0805")
      (description "Resistor")
      (fields (field (name "PUBLISHER") "Altium Limited"))
      (libsource (lib "") (part "Res2_1"))
    )
    (comp (ref "R66")
      (value "4.7K")
      (footprint "0805")
      (description "Resistor")
      (fields (field (name "PUBLISHER") "Altium Limited"))
      (libsource (lib "") (part "Res2_3"))
    )
    (comp (ref "R67")
      (value "4.7K")
      (footprint "0805")
      (description "Resistor")
      (fields (field (name "PUBLISHER") "Altium Limited"))
      (libsource (lib "") (part "Res2_3"))
    )
    (comp (ref "R68")
      (value "1K")
      (footprint "0805")
      (description "Resistor")
      (fields (field (name "PUBLISHER") "Altium Limited"))
      (libsource (lib "") (part "Res2_1"))
    )
    (comp (ref "R69")
      (value "4.7K")
      (footprint "0805")
      (description "Resistor")
      (fields (field (name "PUBLISHER") "Altium Limited"))
      (libsource (lib "") (part "Res2_3"))
    )
    (comp (ref "R70")
      (value "4.7K")
      (footprint "0805")
      (description "Resistor")
      (fields (field (name "PUBLISHER") "Altium Limited"))
      (libsource (lib "") (part "Res2_3"))
    )
    (comp (ref "R71")
      (value "1K")
      (footprint "0805")
      (description "Resistor")
      (fields (field (name "PUBLISHER") "Altium Limited"))
      (libsource (lib "") (part "Res2_1"))
    )
    (comp (ref "R72")
      (value "2.2K")
      (footprint "0805")
      (description "Resistor")
      (fields (field (name "PUBLISHER") "Altium Limited"))
      (libsource (lib "") (part "Res2_1"))
    )
    (comp (ref "R73")
      (value "1K")
      (footprint "0805")
      (description "Resistor")
      (fields (field (name "PUBLISHER") "Altium Limited"))
      (libsource (lib "") (part "Res2_2"))
    )
    (comp (ref "R74")
      (value "470R")
      (footprint "0805")
      (description "Resistor")
      (fields (field (name "PUBLISHER") "Altium Limited"))
      (libsource (lib "Miscellaneous Devices") (part "Res2"))
    )
    (comp (ref "R75")
      (value "470R")
      (footprint "0805")
      (description "Resistor")
      (fields (field (name "PUBLISHER") "Altium Limited"))
      (libsource (lib "Miscellaneous Devices") (part "Res2"))
    )
    (comp (ref "R76")
      (value "470R")
      (footprint "0805")
      (description "Resistor")
      (fields (field (name "PUBLISHER") "Altium Limited"))
      (libsource (lib "Miscellaneous Devices") (part "Res2"))
    )
    (comp (ref "R77")
      (value "470R")
      (footprint "0805")
      (description "Resistor")
      (fields (field (name "PUBLISHER") "Altium Limited"))
      (libsource (lib "Miscellaneous Devices") (part "Res2"))
    )
    (comp (ref "R78")
      (value "4.7K")
      (footprint "0805")
      (description "Resistor")
      (fields (field (name "PUBLISHER") "Altium Limited"))
      (libsource (lib "") (part "Res2_3"))
    )
    (comp (ref "R79")
      (value "4.7K")
      (footprint "0805")
      (description "Resistor")
      (fields (field (name "PUBLISHER") "Altium Limited"))
      (libsource (lib "") (part "Res2_3"))
    )
    (comp (ref "R80")
      (value "1K")
      (footprint "0805")
      (description "Resistor")
      (fields (field (name "PUBLISHER") "Altium Limited"))
      (libsource (lib "") (part "Res2_1"))
    )
    (comp (ref "R81")
      (value "2.2K")
      (footprint "0805")
      (description "Resistor")
      (fields (field (name "PUBLISHER") "Altium Limited"))
      (libsource (lib "") (part "Res2_1"))
    )
    (comp (ref "R82")
      (value "2.2K")
      (footprint "0805")
      (description "Resistor")
      (fields (field (name "PUBLISHER") "Altium Limited"))
      (libsource (lib "") (part "Res2_1"))
    )
    (comp (ref "R83")
      (value "2.2K")
      (footprint "0805")
      (description "Resistor")
      (fields (field (name "PUBLISHER") "Altium Limited"))
      (libsource (lib "") (part "Res2_1"))
    )
    (comp (ref "R84")
      (value "2.2K")
      (footprint "0805")
      (description "Resistor")
      (fields (field (name "PUBLISHER") "Altium Limited"))
      (libsource (lib "") (part "Res2_1"))
    )
    (comp (ref "R85")
      (value "2.2K")
      (footprint "0805")
      (description "Resistor")
      (fields (field (name "PUBLISHER") "Altium Limited"))
      (libsource (lib "") (part "Res2_1"))
    )
    (comp (ref "R86")
      (value "2.2K")
      (footprint "0805")
      (description "Resistor")
      (fields (field (name "PUBLISHER") "Altium Limited"))
      (libsource (lib "") (part "Res2_1"))
    )
    (comp (ref "R87")
      (value "2.2K")
      (footprint "0805")
      (description "Resistor")
      (fields (field (name "PUBLISHER") "Altium Limited"))
      (libsource (lib "") (part "Res2_1"))
    )
    (comp (ref "R88")
      (value "2.2K")
      (footprint "0805")
      (description "Resistor")
      (fields (field (name "PUBLISHER") "Altium Limited"))
      (libsource (lib "") (part "Res2_1"))
    )
    (comp (ref "R89")
      (value "470R")
      (footprint "0805")
      (description "Resistor")
      (fields (field (name "PUBLISHER") "Altium Limited"))
      (libsource (lib "") (part "Res2_3"))
    )
    (comp (ref "R90")
      (value "470R")
      (footprint "0805")
      (description "Resistor")
      (fields (field (name "PUBLISHER") "Altium Limited"))
      (libsource (lib "") (part "Res2_3"))
    )
    (comp (ref "R91")
      (value "470R")
      (footprint "0805")
      (description "Resistor")
      (fields (field (name "PUBLISHER") "Altium Limited"))
      (libsource (lib "") (part "Res2_3"))
    )
    (comp (ref "R92")
      (value "470R")
      (footprint "0805")
      (description "Resistor")
      (fields (field (name "PUBLISHER") "Altium Limited"))
      (libsource (lib "") (part "Res2_3"))
    )
    (comp (ref "R93")
      (value "2.2K")
      (footprint "0805")
      (description "Resistor")
      (fields (field (name "PUBLISHER") "Altium Limited"))
      (libsource (lib "") (part "Res2_1"))
    )
    (comp (ref "R94")
      (value "2.2K")
      (footprint "0805")
      (description "Resistor")
      (fields (field (name "PUBLISHER") "Altium Limited"))
      (libsource (lib "") (part "Res2_1"))
    )
    (comp (ref "R95")
      (value "2.2K")
      (footprint "0805")
      (description "Resistor")
      (fields (field (name "PUBLISHER") "Altium Limited"))
      (libsource (lib "") (part "Res2_1"))
    )
    (comp (ref "R96")
      (value "2.2K")
      (footprint "0805")
      (description "Resistor")
      (fields (field (name "PUBLISHER") "Altium Limited"))
      (libsource (lib "") (part "Res2_1"))
    )
    (comp (ref "R97")
      (value "2.2K")
      (footprint "0805")
      (description "Resistor")
      (fields (field (name "PUBLISHER") "Altium Limited"))
      (libsource (lib "") (part "Res2_1"))
    )
    (comp (ref "R98")
      (value "2.2K")
      (footprint "0805")
      (description "Resistor")
      (fields (field (name "PUBLISHER") "Altium Limited"))
      (libsource (lib "") (part "Res2_1"))
    )
    (comp (ref "R99")
      (value "2.2K")
      (footprint "0805")
      (description "Resistor")
      (fields (field (name "PUBLISHER") "Altium Limited"))
      (libsource (lib "") (part "Res2_1"))
    )
    (comp (ref "R100")
      (value "2.2K")
      (footprint "0805")
      (description "Resistor")
      (fields (field (name "PUBLISHER") "Altium Limited"))
      (libsource (lib "") (part "Res2_1"))
    )
    (comp (ref "R101")
      (value "10K")
      (footprint "0805")
      (description "Resistor")
      (fields (field (name "PUBLISHER") "Altium Limited"))
      (libsource (lib "Miscellaneous Devices") (part "Res2"))
    )
    (comp (ref "R102")
      (value "10K")
      (footprint "0805")
      (description "Resistor")
      (fields (field (name "PUBLISHER") "Altium Limited"))
      (libsource (lib "Miscellaneous Devices") (part "Res2"))
    )
    (comp (ref "R103")
      (value "470R")
      (footprint "0805")
      (description "Resistor")
      (fields (field (name "PUBLISHER") "Altium Limited"))
      (libsource (lib "Miscellaneous Devices") (part "Res2"))
    )
    (comp (ref "R104")
      (value "470R")
      (footprint "0805")
      (description "Resistor")
      (fields (field (name "PUBLISHER") "Altium Limited"))
      (libsource (lib "Miscellaneous Devices") (part "Res2"))
    )
    (comp (ref "R105")
      (value "470R")
      (footprint "0805")
      (description "Resistor")
      (fields (field (name "PUBLISHER") "Altium Limited"))
      (libsource (lib "Miscellaneous Devices") (part "Res2"))
    )
    (comp (ref "R106")
      (value "470R")
      (footprint "0805")
      (description "Resistor")
      (fields (field (name "PUBLISHER") "Altium Limited"))
      (libsource (lib "Miscellaneous Devices") (part "Res2"))
    )
    (comp (ref "R107")
      (value "2.2K")
      (footprint "0805")
      (description "Resistor")
      (fields (field (name "PUBLISHER") "Altium Limited"))
      (libsource (lib "") (part "Res2_1"))
    )
    (comp (ref "R108")
      (value "2.2K")
      (footprint "0805")
      (description "Resistor")
      (fields (field (name "PUBLISHER") "Altium Limited"))
      (libsource (lib "") (part "Res2_1"))
    )
    (comp (ref "R109")
      (value "2.2K")
      (footprint "0805")
      (description "Resistor")
      (fields (field (name "PUBLISHER") "Altium Limited"))
      (libsource (lib "") (part "Res2_1"))
    )
    (comp (ref "R110")
      (value "2.2K")
      (footprint "0805")
      (description "Resistor")
      (fields (field (name "PUBLISHER") "Altium Limited"))
      (libsource (lib "") (part "Res2_1"))
    )
    (comp (ref "R111")
      (value "2.2K")
      (footprint "0805")
      (description "Resistor")
      (fields (field (name "PUBLISHER") "Altium Limited"))
      (libsource (lib "") (part "Res2_1"))
    )
    (comp (ref "R112")
      (value "2.2K")
      (footprint "0805")
      (description "Resistor")
      (fields (field (name "PUBLISHER") "Altium Limited"))
      (libsource (lib "") (part "Res2_1"))
    )
    (comp (ref "R113")
      (value "2.2K")
      (footprint "0805")
      (description "Resistor")
      (fields (field (name "PUBLISHER") "Altium Limited"))
      (libsource (lib "") (part "Res2_1"))
    )
    (comp (ref "R114")
      (value "2.2K")
      (footprint "0805")
      (description "Resistor")
      (fields (field (name "PUBLISHER") "Altium Limited"))
      (libsource (lib "") (part "Res2_1"))
    )
    (comp (ref "R115")
      (value "2.2K")
      (footprint "0805")
      (description "Resistor")
      (fields (field (name "PUBLISHER") "Altium Limited"))
      (libsource (lib "") (part "Res2_1"))
    )
    (comp (ref "R116")
      (value "2.2K")
      (footprint "0805")
      (description "Resistor")
      (fields (field (name "PUBLISHER") "Altium Limited"))
      (libsource (lib "") (part "Res2_1"))
    )
    (comp (ref "R117")
      (value "2.2K")
      (footprint "0805")
      (description "Resistor")
      (fields (field (name "PUBLISHER") "Altium Limited"))
      (libsource (lib "") (part "Res2_1"))
    )
    (comp (ref "R118")
      (value "2.2K")
      (footprint "0805")
      (description "Resistor")
      (fields (field (name "PUBLISHER") "Altium Limited"))
      (libsource (lib "") (part "Res2_1"))
    )
    (comp (ref "R119")
      (value "2.2K")
      (footprint "0805")
      (description "Resistor")
      (fields (field (name "PUBLISHER") "Altium Limited"))
      (libsource (lib "") (part "Res2_1"))
    )
    (comp (ref "R120")
      (value "2.2K")
      (footprint "0805")
      (description "Resistor")
      (fields (field (name "PUBLISHER") "Altium Limited"))
      (libsource (lib "") (part "Res2_1"))
    )
    (comp (ref "R121")
      (value "2.2K")
      (footprint "0805")
      (description "Resistor")
      (fields (field (name "PUBLISHER") "Altium Limited"))
      (libsource (lib "") (part "Res2_1"))
    )
    (comp (ref "R122")
      (value "2.2K")
      (footprint "0805")
      (description "Resistor")
      (fields (field (name "PUBLISHER") "Altium Limited"))
      (libsource (lib "") (part "Res2_1"))
    )
    (comp (ref "R123")
      (value "470R")
      (footprint "0805")
      (description "Resistor")
      (fields (field (name "Comment") "Res2") (field (name "PUBLISHER") "Altium Limited"))
      (libsource (lib "") (part "Res2_2"))
    )
    (comp (ref "R124")
      (value "470R")
      (footprint "0805")
      (description "Resistor")
      (fields (field (name "Comment") "Res2") (field (name "PUBLISHER") "Altium Limited"))
      (libsource (lib "") (part "Res2_2"))
    )
    (comp (ref "R125")
      (value "470R")
      (footprint "0805")
      (description "Resistor")
      (fields (field (name "PUBLISHER") "Altium Limited"))
      (libsource (lib "") (part "Res2_3"))
    )
    (comp (ref "R126")
      (value "470R")
      (footprint "0805")
      (description "Resistor")
      (fields (field (name "PUBLISHER") "Altium Limited"))
      (libsource (lib "") (part "Res2_3"))
    )
    (comp (ref "R127")
      (value "4.7K")
      (footprint "0805")
      (description "Resistor")
      (fields (field (name "PUBLISHER") "Altium Limited"))
      (libsource (lib "") (part "Res2_3"))
    )
    (comp (ref "R128")
      (value "4.7K")
      (footprint "0805")
      (description "Resistor")
      (fields (field (name "PUBLISHER") "Altium Limited"))
      (libsource (lib "") (part "Res2_3"))
    )
    (comp (ref "R129")
      (value "4.7K")
      (footprint "0805")
      (description "Resistor")
      (fields (field (name "PUBLISHER") "Altium Limited"))
      (libsource (lib "") (part "Res2_3"))
    )
    (comp (ref "R130")
      (value "4.7K")
      (footprint "0805")
      (description "Resistor")
      (fields (field (name "PUBLISHER") "Altium Limited"))
      (libsource (lib "") (part "Res2_3"))
    )
    (comp (ref "R131")
      (value "1K")
      (footprint "0805")
      (description "Resistor")
      (fields (field (name "PUBLISHER") "Altium Limited"))
      (libsource (lib "") (part "Res2_1"))
    )
    (comp (ref "R132")
      (value "1K")
      (footprint "0805")
      (description "Resistor")
      (fields (field (name "PUBLISHER") "Altium Limited"))
      (libsource (lib "") (part "Res2_1"))
    )
    (comp (ref "R133")
      (value "4.7K")
      (footprint "0805")
      (description "Resistor")
      (fields (field (name "PUBLISHER") "Altium Limited"))
      (libsource (lib "") (part "Res2_3"))
    )
    (comp (ref "R134")
      (value "4.7K")
      (footprint "0805")
      (description "Resistor")
      (fields (field (name "PUBLISHER") "Altium Limited"))
      (libsource (lib "") (part "Res2_3"))
    )
    (comp (ref "R135")
      (value "4.7K")
      (footprint "0805")
      (description "Resistor")
      (fields (field (name "PUBLISHER") "Altium Limited"))
      (libsource (lib "") (part "Res2_3"))
    )
    (comp (ref "R136")
      (value "4.7K")
      (footprint "0805")
      (description "Resistor")
      (fields (field (name "PUBLISHER") "Altium Limited"))
      (libsource (lib "") (part "Res2_3"))
    )
    (comp (ref "R137")
      (value "10K")
      (footprint "0805")
      (description "Resistor")
      (fields (field (name "PUBLISHER") "Altium Limited"))
      (libsource (lib "Miscellaneous Devices") (part "Res2"))
    )
    (comp (ref "R138")
      (value "10K")
      (footprint "0805")
      (description "Resistor")
      (fields (field (name "PUBLISHER") "Altium Limited"))
      (libsource (lib "") (part "Res2_1"))
    )
    (comp (ref "R139")
      (value "10K")
      (footprint "0805")
      (description "Resistor")
      (fields (field (name "PUBLISHER") "Altium Limited"))
      (libsource (lib "") (part "Res2_1"))
    )
    (comp (ref "R140")
      (value "1K")
      (footprint "0805")
      (description "Resistor")
      (fields (field (name "PUBLISHER") "Altium Limited"))
      (libsource (lib "Miscellaneous Devices") (part "Res2"))
    )
    (comp (ref "R141")
      (value "10K")
      (footprint "0805")
      (description "Resistor")
      (fields (field (name "PUBLISHER") "Altium Limited"))
      (libsource (lib "") (part "Res2_1"))
    )
    (comp (ref "U1")
      (value "B2405XT-2WR2")
      (footprint "B2405XT-2WR2")
      (libsource (lib "原理图元件库") (part "B2405XT-2WR2"))
    )
    (comp (ref "U2")
      (value "AMS1117-3.3")
      (footprint "SOT223")
      (libsource (lib "货架电子标签元件库") (part "AMS1117-5"))
    )
    (comp (ref "U3")
      (value "MAX3232CSE")
      (footprint "SOIC-16_150mil")
      (description "3.0V TO 5.5V, Low-Power, up to 1Mbps, True RS-232 Transceiver Using Four 0.1礔 External Capacitor")
      (fields (field (name "PUBLISHER") "Altium Limited"))
      (libsource (lib "Maxim Communication Transceiver") (part "MAX3232CSE"))
    )
    (comp (ref "U4") (value "USR-K") (footprint "USR-K") (libsource (lib "原理图元件库") (part "USR-K")))
    (comp (ref "U5")
      (value "STM32F103RCT6")
      (footprint "LQFP64_M")
      (libsource (lib "原理图元件库") (part "STM32F103RCT6"))
    )
    (comp (ref "U6")
      (value "MAX3485")
      (footprint "AT24C512")
      (description "Low-Power, Slew-Rate-Limited RS-485/RS-422 Transceiver")
      (fields (field (name "PUBLISHER") "Altium Limited"))
      (libsource (lib "Maxim Communication Transceiver") (part "MAX485CSA"))
    )
    (comp (ref "U7") (value "TLP280-4") (footprint "SO16") (libsource (lib "WH V20") (part "TLP521-4")))
    (comp (ref "U8")
      (value "MAX3485")
      (footprint "AT24C512")
      (description "Low-Power, Slew-Rate-Limited RS-485/RS-422 Transceiver")
      (fields (field (name "PUBLISHER") "Altium Limited"))
      (libsource (lib "Maxim Communication Transceiver") (part "MAX485CSA"))
    )
    (comp (ref "U9") (value "TLP280-4") (footprint "SO16") (libsource (lib "WH V20") (part "TLP521-4")))
    (comp (ref "U10")
      (value "LM293")
      (footprint "SOIC-8_150mil")
      (libsource (lib "myIntegrated_Library1") (part "LM293"))
    )
    (comp (ref "U11") (value "TLP280-4") (footprint "SO16") (libsource (lib "WH V20") (part "TLP521-4")))
    (comp (ref "U13") (value "TLP280-4") (footprint "SO16") (libsource (lib "WH V20") (part "TLP521-4")))
    (comp (ref "U14") (value "TLP280-4") (footprint "SO16") (libsource (lib "WH V20") (part "TLP521-4")))
    (comp (ref "U15") (value "TLP280-4") (footprint "SO16") (libsource (lib "WH V20") (part "TLP521-4")))
    (comp (ref "U16") (value "TLP280-4") (footprint "SO16") (libsource (lib "WH V20") (part "TLP521-4")))
    (comp (ref "U17") (value "TLP280-4") (footprint "SO16") (libsource (lib "WH V20") (part "TLP521-4")))
    (comp (ref "U19") (value "TLP280-4") (footprint "SO16") (libsource (lib "WH V20") (part "TLP521-4")))
    (comp (ref "W1")
      (value "Jumper")
      (footprint "HDR1X2")
      (description "Jumper Wire")
      (fields (field (name "PUBLISHER") "Altium Limited"))
      (libsource (lib "Miscellaneous Devices") (part "Jumper"))
    )
    (comp (ref "W2")
      (value "Jumper")
      (footprint "HDR1X2")
      (description "Jumper Wire")
      (fields (field (name "PUBLISHER") "Altium Limited"))
      (libsource (lib "Miscellaneous Devices") (part "Jumper"))
    )
    (comp (ref "Y1") (value "8M") (footprint "Footprint:XTAL") (libsource (lib "Schlib1") (part "XTAL_1")))
  )
  (nets
    (net (code "1") (name "+3.3V") (class "Default")
      (node (ref "C1") (pin "2") (pinfunction "2_2") (pintype "passive"))
      (node (ref "C13") (pin "1") (pinfunction "1_1") (pintype "passive"))
      (node (ref "C14") (pin "2") (pinfunction "2_2") (pintype "passive"))
      (node (ref "C15") (pin "2") (pinfunction "2_2") (pintype "passive"))
      (node (ref "C17") (pin "2") (pinfunction "2_2") (pintype "passive"))
      (node (ref "C19") (pin "2") (pinfunction "2_2") (pintype "passive"))
      (node (ref "C20") (pin "2") (pinfunction "2_2") (pintype "passive"))
      (node (ref "C21") (pin "2") (pinfunction "2_2") (pintype "passive"))
      (node (ref "C23") (pin "1") (pinfunction "1_1") (pintype "passive"))
      (node (ref "C28") (pin "1") (pinfunction "1_1") (pintype "passive"))
      (node (ref "C6") (pin "1") (pinfunction "1_1") (pintype "passive"))
      (node (ref "C7") (pin "2") (pinfunction "2_2") (pintype "passive"))
      (node (ref "C9") (pin "1") (pinfunction "1_1") (pintype "passive"))
      (node (ref "D4") (pin "1") (pinfunction "A_1") (pintype "passive"))
      (node (ref "F2") (pin "2") (pinfunction "2_2") (pintype "passive"))
      (node (ref "JP1") (pin "1") (pinfunction "1_1") (pintype "passive"))
      (node (ref "P6") (pin "1") (pinfunction "1_1") (pintype "passive"))
      (node (ref "R1") (pin "1") (pinfunction "1_1") (pintype "passive"))
      (node (ref "R10") (pin "1") (pinfunction "1_1") (pintype "passive"))
      (node (ref "R103") (pin "2") (pinfunction "2_2") (pintype "passive"))
      (node (ref "R104") (pin "2") (pinfunction "2_2") (pintype "passive"))
      (node (ref "R105") (pin "2") (pinfunction "2_2") (pintype "passive"))
      (node (ref "R106") (pin "2") (pinfunction "2_2") (pintype "passive"))
      (node (ref "R11") (pin "1") (pinfunction "1_1") (pintype "passive"))
      (node (ref "R123") (pin "2") (pinfunction "2_2") (pintype "passive"))
      (node (ref "R124") (pin "2") (pinfunction "2_2") (pintype "passive"))
      (node (ref "R125") (pin "1") (pinfunction "1_1") (pintype "passive"))
      (node (ref "R126") (pin "1") (pinfunction "1_1") (pintype "passive"))
      (node (ref "R13") (pin "1") (pinfunction "1_1") (pintype "passive"))
      (node (ref "R133") (pin "1") (pinfunction "1_1") (pintype "passive"))
      (node (ref "R135") (pin "1") (pinfunction "1_1") (pintype "passive"))
      (node (ref "R14") (pin "1") (pinfunction "1_1") (pintype "passive"))
      (node (ref "R16") (pin "2") (pinfunction "2_2") (pintype "passive"))
      (node (ref "R17") (pin "1") (pinfunction "1_1") (pintype "passive"))
      (node (ref "R18") (pin "1") (pinfunction "1_1") (pintype "passive"))
      (node (ref "R19") (pin "1") (pinfunction "1_1") (pintype "passive"))
      (node (ref "R2") (pin "1") (pinfunction "1_1") (pintype "passive"))
      (node (ref "R28") (pin "1") (pinfunction "1_1") (pintype "passive"))
      (node (ref "R29") (pin "1") (pinfunction "1_1") (pintype "passive"))
      (node (ref "R3") (pin "1") (pinfunction "1_1") (pintype "passive"))
      (node (ref "R34") (pin "1") (pinfunction "1_1") (pintype "passive"))
      (node (ref "R35") (pin "1") (pinfunction "1_1") (pintype "passive"))
      (node (ref "R37") (pin "1") (pinfunction "1_1") (pintype "passive"))
      (node (ref "R38") (pin "1") (pinfunction "1_1") (pintype "passive"))
      (node (ref "R39") (pin "2") (pinfunction "2_2") (pintype "passive"))
      (node (ref "R4") (pin "1") (pinfunction "1_1") (pintype "passive"))
      (node (ref "R5") (pin "1") (pinfunction "1_1") (pintype "passive"))
      (node (ref "R52") (pin "1") (pinfunction "1_1") (pintype "passive"))
      (node (ref "R6") (pin "1") (pinfunction "1_1") (pintype "passive"))
      (node (ref "R74") (pin "2") (pinfunction "2_2") (pintype "passive"))
      (node (ref "R75") (pin "2") (pinfunction "2_2") (pintype "passive"))
      (node (ref "R76") (pin "2") (pinfunction "2_2") (pintype "passive"))
      (node (ref "R77") (pin "2") (pinfunction "2_2") (pintype "passive"))
      (node (ref "R8") (pin "1") (pinfunction "1_1") (pintype "passive"))
      (node (ref "R89") (pin "1") (pinfunction "1_1") (pintype "passive"))
      (node (ref "R9") (pin "1") (pinfunction "1_1") (pintype "passive"))
      (node (ref "R90") (pin "1") (pinfunction "1_1") (pintype "passive"))
      (node (ref "R91") (pin "1") (pinfunction "1_1") (pintype "passive"))
      (node (ref "R92") (pin "1") (pinfunction "1_1") (pintype "passive"))
      (node (ref "U16") (pin "10") (pinfunction "C_10") (pintype "passive"))
      (node (ref "U16") (pin "12") (pinfunction "C_12") (pintype "passive"))
      (node (ref "U16") (pin "14") (pinfunction "C_14") (pintype "passive"))
      (node (ref "U16") (pin "16") (pinfunction "C_16") (pintype "passive"))
      (node (ref "U17") (pin "12") (pinfunction "C_12") (pintype "passive"))
      (node (ref "U17") (pin "14") (pinfunction "C_14") (pintype "passive"))
      (node (ref "U17") (pin "16") (pinfunction "C_16") (pintype "passive"))
      (node (ref "U3") (pin "16") (pinfunction "VCC_16") (pintype "power_in"))
      (node (ref "U4") (pin "11") (pinfunction "VCC_3V3_11") (pintype "passive"))
      (node (ref "U4") (pin "14") (pinfunction "LED_3V3_14") (pintype "passive"))
      (node (ref "U4") (pin "15") (pinfunction "LED_3V3_15") (pintype "passive"))
      (node (ref "U5") (pin "13") (pinfunction "VDDA_13") (pintype "power_in"))
      (node (ref "U5") (pin "19") (pinfunction "VDD_4_19") (pintype "power_in"))
      (node (ref "U5") (pin "32") (pinfunction "VDD_1_32") (pintype "power_in"))
      (node (ref "U5") (pin "48") (pinfunction "VDD_2_48") (pintype "power_in"))
      (node (ref "U5") (pin "64") (pinfunction "VDD_3_64") (pintype "power_in"))
      (node (ref "U6") (pin "8") (pinfunction "VCC_8") (pintype "power_in"))
      (node (ref "U8") (pin "8") (pinfunction "VCC_8") (pintype "power_in"))
      (node (ref "U9") (pin "10") (pinfunction "C_10") (pintype "passive"))
      (node (ref "U9") (pin "12") (pinfunction "C_12") (pintype "passive"))
      (node (ref "U9") (pin "14") (pinfunction "C_14") (pintype "passive"))
      (node (ref "U9") (pin "16") (pinfunction "C_16") (pintype "passive"))
    )
    (net (code "2") (name "+5V") (class "Default")
      (node (ref "C33") (pin "2") (pinfunction "2_2") (pintype "passive"))
      (node (ref "C4") (pin "1") (pinfunction "1_1") (pintype "passive"))
      (node (ref "C5") (pin "2") (pinfunction "2_2") (pintype "passive"))
      (node (ref "P5") (pin "1") (pinfunction "1_1") (pintype "passive"))
      (node (ref "R138") (pin "2") (pinfunction "2_2") (pintype "passive"))
      (node (ref "R139") (pin "2") (pinfunction "2_2") (pintype "passive"))
      (node (ref "R140") (pin "1") (pinfunction "1_1") (pintype "passive"))
      (node (ref "R141") (pin "2") (pinfunction "2_2") (pintype "passive"))
      (node (ref "R73") (pin "1") (pinfunction "1_1") (pintype "passive"))
      (node (ref "U1") (pin "5") (pinfunction "+Vo_5") (pintype "passive"))
      (node (ref "U10") (pin "8") (pinfunction "VCC_8") (pintype "passive"))
      (node (ref "U2") (pin "3") (pinfunction "Vin_3") (pintype "passive"))
    )
    (net (code "3") (name "+24V") (class "Default")
      (node (ref "C2") (pin "1") (pinfunction "1_1") (pintype "passive"))
      (node (ref "C3") (pin "2") (pinfunction "2_2") (pintype "passive"))
      (node (ref "C36") (pin "1") (pinfunction "1_1") (pintype "passive"))
      (node (ref "D1") (pin "2") (pinfunction "K_2") (pintype "passive"))
      (node (ref "F1") (pin "2") (pinfunction "2_2") (pintype "passive"))
      (node (ref "F3") (pin "2") (pinfunction "2_2") (pintype "passive"))
      (node (ref "F4") (pin "2") (pinfunction "2_2") (pintype "passive"))
      (node (ref "P12") (pin "1") (pinfunction "1_1") (pintype "passive"))
      (node (ref "P13") (pin "1") (pinfunction "1_1") (pintype "passive"))
      (node (ref "P2") (pin "1") (pinfunction "1_1") (pintype "passive"))
      (node (ref "P3") (pin "1") (pinfunction "1_1") (pintype "passive"))
      (node (ref "P7") (pin "1") (pinfunction "1_1") (pintype "passive"))
      (node (ref "Q10") (pin "3") (pinfunction "S_3") (pintype "passive"))
      (node (ref "Q13") (pin "3") (pinfunction "S_3") (pintype "passive"))
      (node (ref "Q14") (pin "3") (pinfunction "S_3") (pintype "passive"))
      (node (ref "Q25") (pin "3") (pinfunction "S_3") (pintype "passive"))
      (node (ref "Q26") (pin "3") (pinfunction "S_3") (pintype "passive"))
      (node (ref "Q5") (pin "3") (pinfunction "S_3") (pintype "passive"))
      (node (ref "Q8") (pin "3") (pinfunction "S_3") (pintype "passive"))
      (node (ref "Q9") (pin "3") (pinfunction "S_3") (pintype "passive"))
      (node (ref "R107") (pin "2") (pinfunction "2_2") (pintype "passive"))
      (node (ref "R108") (pin "2") (pinfunction "2_2") (pintype "passive"))
      (node (ref "R109") (pin "2") (pinfunction "2_2") (pintype "passive"))
      (node (ref "R110") (pin "2") (pinfunction "2_2") (pintype "passive"))
      (node (ref "R117") (pin "2") (pinfunction "2_2") (pintype "passive"))
      (node (ref "R118") (pin "2") (pinfunction "2_2") (pintype "passive"))
      (node (ref "R119") (pin "2") (pinfunction "2_2") (pintype "passive"))
      (node (ref "R120") (pin "2") (pinfunction "2_2") (pintype "passive"))
      (node (ref "R127") (pin "1") (pinfunction "1_1") (pintype "passive"))
      (node (ref "R128") (pin "1") (pinfunction "1_1") (pintype "passive"))
      (node (ref "R129") (pin "1") (pinfunction "1_1") (pintype "passive"))
      (node (ref "R130") (pin "1") (pinfunction "1_1") (pintype "passive"))
      (node (ref "R24") (pin "2") (pinfunction "2_2") (pintype "passive"))
      (node (ref "R25") (pin "2") (pinfunction "2_2") (pintype "passive"))
      (node (ref "R26") (pin "2") (pinfunction "2_2") (pintype "passive"))
      (node (ref "R27") (pin "2") (pinfunction "2_2") (pintype "passive"))
      (node (ref "R42") (pin "1") (pinfunction "1_1") (pintype "passive"))
      (node (ref "R43") (pin "1") (pinfunction "1_1") (pintype "passive"))
      (node (ref "R46") (pin "1") (pinfunction "1_1") (pintype "passive"))
      (node (ref "R47") (pin "1") (pinfunction "1_1") (pintype "passive"))
      (node (ref "R55") (pin "2") (pinfunction "2_2") (pintype "passive"))
      (node (ref "R56") (pin "2") (pinfunction "2_2") (pintype "passive"))
      (node (ref "R57") (pin "2") (pinfunction "2_2") (pintype "passive"))
      (node (ref "R58") (pin "2") (pinfunction "2_2") (pintype "passive"))
      (node (ref "R60") (pin "1") (pinfunction "1_1") (pintype "passive"))
      (node (ref "R61") (pin "1") (pinfunction "1_1") (pintype "passive"))
      (node (ref "R63") (pin "1") (pinfunction "1_1") (pintype "passive"))
      (node (ref "R64") (pin "1") (pinfunction "1_1") (pintype "passive"))
      (node (ref "R66") (pin "1") (pinfunction "1_1") (pintype "passive"))
      (node (ref "R67") (pin "1") (pinfunction "1_1") (pintype "passive"))
      (node (ref "R69") (pin "1") (pinfunction "1_1") (pintype "passive"))
      (node (ref "R70") (pin "1") (pinfunction "1_1") (pintype "passive"))
      (node (ref "R78") (pin "1") (pinfunction "1_1") (pintype "passive"))
      (node (ref "R79") (pin "1") (pinfunction "1_1") (pintype "passive"))
      (node (ref "R82") (pin "2") (pinfunction "2_2") (pintype "passive"))
      (node (ref "R83") (pin "2") (pinfunction "2_2") (pintype "passive"))
      (node (ref "R85") (pin "2") (pinfunction "2_2") (pintype "passive"))
      (node (ref "R87") (pin "2") (pinfunction "2_2") (pintype "passive"))
      (node (ref "R93") (pin "2") (pinfunction "2_2") (pintype "passive"))
      (node (ref "R95") (pin "2") (pinfunction "2_2") (pintype "passive"))
      (node (ref "R96") (pin "2") (pinfunction "2_2") (pintype "passive"))
      (node (ref "R97") (pin "2") (pinfunction "2_2") (pintype "passive"))
      (node (ref "U1") (pin "2") (pinfunction "Vin_2") (pintype "passive"))
    )
    (net (code "4") (name "+24Vin") (class "Default")
      (node (ref "F1") (pin "1") (pinfunction "1_1") (pintype "passive"))
      (node (ref "P1") (pin "1") (pinfunction "1_1") (pintype "passive"))
      (node (ref "P10") (pin "3") (pinfunction "3_3") (pintype "passive"))
      (node (ref "P10") (pin "4") (pinfunction "4_4") (pintype "passive"))
      (node (ref "P11") (pin "3") (pinfunction "3_3") (pintype "passive"))
      (node (ref "P11") (pin "4") (pinfunction "4_4") (pintype "passive"))
    )
    (net (code "5") (name "/2V5") (class "Default")
      (node (ref "R137") (pin "1") (pinfunction "1_1") (pintype "passive"))
      (node (ref "R138") (pin "1") (pinfunction "1_1") (pintype "passive"))
      (node (ref "U10") (pin "2") (pinfunction "1IN-_2") (pintype "passive"))
      (node (ref "U10") (pin "6") (pinfunction "2IN-_6") (pintype "passive"))
    )
    (net (code "6") (name "/A1") (class "Default")
      (node (ref "C31") (pin "2") (pinfunction "2_2") (pintype "passive"))
      (node (ref "D6") (pin "1") (pinfunction "A_1") (pintype "passive"))
      (node (ref "D7") (pin "2") (pinfunction "K_2") (pintype "passive"))
      (node (ref "LED14") (pin "2") (pinfunction "K_2") (pintype "passive"))
      (node (ref "LED16") (pin "1") (pinfunction "A_1") (pintype "passive"))
      (node (ref "P12") (pin "3") (pinfunction "3_3") (pintype "passive"))
      (node (ref "Q15") (pin "2") (pinfunction "D_2") (pintype "passive"))
      (node (ref "Q17") (pin "2") (pinfunction "D_2") (pintype "passive"))
    )
    (net (code "7") (name "/A2") (class "Default")
      (node (ref "C32") (pin "2") (pinfunction "2_2") (pintype "passive"))
      (node (ref "D10") (pin "1") (pinfunction "A_1") (pintype "passive"))
      (node (ref "D11") (pin "2") (pinfunction "K_2") (pintype "passive"))
      (node (ref "LED15") (pin "2") (pinfunction "K_2") (pintype "passive"))
      (node (ref "LED17") (pin "1") (pinfunction "A_1") (pintype "passive"))
      (node (ref "P13") (pin "3") (pinfunction "3_3") (pintype "passive"))
      (node (ref "Q16") (pin "2") (pinfunction "D_2") (pintype "passive"))
      (node (ref "Q18") (pin "2") (pinfunction "D_2") (pintype "passive"))
    )
    (net (code "8") (name "/B1") (class "Default")
      (node (ref "C31") (pin "1") (pinfunction "1_1") (pintype "passive"))
      (node (ref "D8") (pin "1") (pinfunction "A_1") (pintype "passive"))
      (node (ref "D9") (pin "2") (pinfunction "K_2") (pintype "passive"))
      (node (ref "P12") (pin "4") (pinfunction "4_4") (pintype "passive"))
      (node (ref "Q19") (pin "2") (pinfunction "D_2") (pintype "passive"))
      (node (ref "Q20") (pin "2") (pinfunction "D_2") (pintype "passive"))
      (node (ref "R101") (pin "1") (pinfunction "1_1") (pintype "passive"))
    )
    (net (code "9") (name "/B2") (class "Default")
      (node (ref "C32") (pin "1") (pinfunction "1_1") (pintype "passive"))
      (node (ref "D12") (pin "1") (pinfunction "A_1") (pintype "passive"))
      (node (ref "D13") (pin "2") (pinfunction "K_2") (pintype "passive"))
      (node (ref "P13") (pin "4") (pinfunction "4_4") (pintype "passive"))
      (node (ref "Q21") (pin "2") (pinfunction "D_2") (pintype "passive"))
      (node (ref "Q22") (pin "2") (pinfunction "D_2") (pintype "passive"))
      (node (ref "R102") (pin "1") (pinfunction "1_1") (pintype "passive"))
    )
    (net (code "10") (name "/DATA") (class "Default")
      (node (ref "P6") (pin "2") (pinfunction "2_2") (pintype "passive"))
      (node (ref "R8") (pin "2") (pinfunction "2_2") (pintype "passive"))
      (node (ref "U5") (pin "58") (pinfunction "PB6/I2C1_SDA/TIM4_CH1_58") (pintype "bidirectional"))
    )
    (net (code "11") (name "/DIR1") (class "Default")
      (node (ref "P4") (pin "2") (pinfunction "2_2") (pintype "passive"))
      (node (ref "Q4") (pin "2") (pinfunction "D_2") (pintype "passive"))
      (node (ref "Q5") (pin "2") (pinfunction "D_2") (pintype "passive"))
    )
    (net (code "12") (name "/DIR1_OUT") (class "Default")
      (node (ref "U5") (pin "14") (pinfunction "PA0-WKUP/TIM2_CH1_14") (pintype "bidirectional"))
      (node (ref "U7") (pin "6") (pinfunction "K_6") (pintype "passive"))
      (node (ref "U7") (pin "8") (pinfunction "K_8") (pintype "passive"))
    )
    (net (code "13") (name "/DIR2") (class "Default")
      (node (ref "P4") (pin "4") (pinfunction "4_4") (pintype "passive"))
      (node (ref "Q10") (pin "2") (pinfunction "D_2") (pintype "passive"))
      (node (ref "Q7") (pin "2") (pinfunction "D_2") (pintype "passive"))
    )
    (net (code "14") (name "/DIR2_OUT") (class "Default")
      (node (ref "U11") (pin "2") (pinfunction "K_2") (pintype "passive"))
      (node (ref "U11") (pin "4") (pinfunction "K_4") (pintype "passive"))
      (node (ref "U5") (pin "20") (pinfunction "PA4_20") (pintype "bidirectional"))
    )
    (net (code "15") (name "/Left-Opposite") (class "Default")
      (node (ref "R80") (pin "2") (pinfunction "2_2") (pintype "passive"))
      (node (ref "U16") (pin "11") (pinfunction "E_11") (pintype "passive"))
      (node (ref "U5") (pin "24") (pinfunction "PC4_24") (pintype "bidirectional"))
    )
    (net (code "16") (name "/Left-OppositeSensor") (class "Default")
      (node (ref "LED22") (pin "2") (pinfunction "K_2") (pintype "passive"))
      (node (ref "P12") (pin "5") (pinfunction "5_5") (pintype "passive"))
      (node (ref "U16") (pin "6") (pinfunction "K_6") (pintype "passive"))
    )
    (net (code "17") (name "/LeftGate-A") (class "Default")
      (node (ref "U14") (pin "2") (pinfunction "K_2") (pintype "passive"))
      (node (ref "U14") (pin "4") (pinfunction "K_4") (pintype "passive"))
      (node (ref "U5") (pin "11") (pinfunction "PC3_11") (pintype "bidirectional"))
    )
    (net (code "18") (name "/LeftGate-B") (class "Default")
      (node (ref "U14") (pin "6") (pinfunction "K_6") (pintype "passive"))
      (node (ref "U14") (pin "8") (pinfunction "K_8") (pintype "passive"))
      (node (ref "U5") (pin "26") (pinfunction "PB0/TIM3_CH3_26") (pintype "bidirectional"))
    )
    (net (code "19") (name "/LeftS-CLOSE") (class "Default")
      (node (ref "R71") (pin "2") (pinfunction "2_2") (pintype "passive"))
      (node (ref "U16") (pin "13") (pinfunction "E_13") (pintype "passive"))
      (node (ref "U5") (pin "23") (pinfunction "PA7/TIM3_CH2_23") (pintype "bidirectional"))
    )
    (net (code "20") (name "/LeftS-OPEN") (class "Default")
      (node (ref "R68") (pin "2") (pinfunction "2_2") (pintype "passive"))
      (node (ref "U16") (pin "15") (pinfunction "E_15") (pintype "passive"))
      (node (ref "U5") (pin "22") (pinfunction "PA6/TIM3_CH1_22") (pintype "bidirectional"))
    )
    (net (code "21") (name "/LeftSensor-CLOSE") (class "Default")
      (node (ref "LED9") (pin "2") (pinfunction "K_2") (pintype "passive"))
      (node (ref "P12") (pin "7") (pinfunction "7_7") (pintype "passive"))
      (node (ref "U16") (pin "4") (pinfunction "K_4") (pintype "passive"))
    )
    (net (code "22") (name "/LeftSensor-OPEN") (class "Default")
      (node (ref "LED8") (pin "2") (pinfunction "K_2") (pintype "passive"))
      (node (ref "P12") (pin "6") (pinfunction "6_6") (pintype "passive"))
      (node (ref "U16") (pin "2") (pinfunction "K_2") (pintype "passive"))
    )
    (net (code "23") (name "/NPN1") (class "Default")
      (node (ref "R48") (pin "2") (pinfunction "2_2") (pintype "passive"))
      (node (ref "U5") (pin "55") (pinfunction "PB3/JTDO_55") (pintype "bidirectional"))
      (node (ref "U9") (pin "15") (pinfunction "E_15") (pintype "passive"))
    )
    (net (code "24") (name "/NPN2") (class "Default")
      (node (ref "R49") (pin "2") (pinfunction "2_2") (pintype "passive"))
      (node (ref "U5") (pin "56") (pinfunction "PB4/JNTRST_56") (pintype "bidirectional"))
      (node (ref "U9") (pin "13") (pinfunction "E_13") (pintype "passive"))
    )
    (net (code "25") (name "/NPNSensor1") (class "Default")
      (node (ref "C24") (pin "2") (pinfunction "2_2") (pintype "passive"))
      (node (ref "LED20") (pin "2") (pinfunction "K_2") (pintype "passive"))
      (node (ref "P7") (pin "3") (pinfunction "3_3") (pintype "passive"))
      (node (ref "U9") (pin "2") (pinfunction "K_2") (pintype "passive"))
    )
    (net (code "26") (name "/NPNSensor2") (class "Default")
      (node (ref "C25") (pin "2") (pinfunction "2_2") (pintype "passive"))
      (node (ref "LED11") (pin "2") (pinfunction "K_2") (pintype "passive"))
      (node (ref "P7") (pin "4") (pinfunction "4_4") (pintype "passive"))
      (node (ref "U9") (pin "4") (pinfunction "K_4") (pintype "passive"))
    )
    (net (code "27") (name "/OSCIN1") (class "Default")
      (node (ref "C18") (pin "2") (pinfunction "2_2") (pintype "passive"))
      (node (ref "R12") (pin "2") (pinfunction "2_2") (pintype "passive"))
      (node (ref "U5") (pin "5") (pinfunction "PD0_OSC32_IN_5") (pintype "input"))
      (node (ref "Y1") (pin "1") (pinfunction "OSC1_1") (pintype "passive"))
    )
    (net (code "28") (name "/OSCOUT1") (class "Default")
      (node (ref "C16") (pin "2") (pinfunction "2_2") (pintype "passive"))
      (node (ref "R12") (pin "1") (pinfunction "1_1") (pintype "passive"))
      (node (ref "U5") (pin "6") (pinfunction "PD1_OSC32_OUT_6") (pintype "output"))
      (node (ref "Y1") (pin "2") (pinfunction "OSC2_2") (pintype "passive"))
    )
    (net (code "29") (name "/OutPutSen") (class "Default")
      (node (ref "R132") (pin "2") (pinfunction "2_2") (pintype "passive"))
      (node (ref "U17") (pin "11") (pinfunction "E_11") (pintype "passive"))
      (node (ref "U5") (pin "41") (pinfunction "PA8/TIM1_CH1_41") (pintype "bidirectional"))
    )
    (net (code "30") (name "/OutPutSensor") (class "Default")
      (node (ref "LED24") (pin "2") (pinfunction "K_2") (pintype "passive"))
      (node (ref "U17") (pin "6") (pinfunction "K_6") (pintype "passive"))
    )
    (net (code "31") (name "/PNP1") (class "Default")
      (node (ref "R50") (pin "2") (pinfunction "2_2") (pintype "passive"))
      (node (ref "U5") (pin "61") (pinfunction "PB8/TIM4_CH3_61") (pintype "bidirectional"))
      (node (ref "U9") (pin "11") (pinfunction "E_11") (pintype "passive"))
    )
    (net (code "32") (name "/PNP2") (class "Default")
      (node (ref "R51") (pin "2") (pinfunction "2_2") (pintype "passive"))
      (node (ref "U5") (pin "62") (pinfunction "PB9/TIM4_CH4_62") (pintype "bidirectional"))
      (node (ref "U9") (pin "9") (pinfunction "E_9") (pintype "passive"))
    )
    (net (code "33") (name "/PNPSensor1") (class "Default")
      (node (ref "C26") (pin "2") (pinfunction "2_2") (pintype "passive"))
      (node (ref "P7") (pin "5") (pinfunction "5_5") (pintype "passive"))
      (node (ref "R40") (pin "1") (pinfunction "1_1") (pintype "passive"))
      (node (ref "R44") (pin "1") (pinfunction "1_1") (pintype "passive"))
    )
    (net (code "34") (name "/PNPSensor2") (class "Default")
      (node (ref "C27") (pin "2") (pinfunction "2_2") (pintype "passive"))
      (node (ref "P7") (pin "6") (pinfunction "6_6") (pintype "passive"))
      (node (ref "R41") (pin "1") (pinfunction "1_1") (pintype "passive"))
      (node (ref "R45") (pin "1") (pinfunction "1_1") (pintype "passive"))
    )
    (net (code "35") (name "/RESET") (class "Default")
      (node (ref "C22") (pin "2") (pinfunction "2_2") (pintype "passive"))
      (node (ref "R6") (pin "2") (pinfunction "2_2") (pintype "passive"))
      (node (ref "U5") (pin "7") (pinfunction "NRST_7") (pintype "bidirectional"))
    )
    (net (code "36") (name "/RS232_RX2") (class "Default")
      (node (ref "P8") (pin "3") (pinfunction "3_3") (pintype "passive"))
      (node (ref "U3") (pin "14") (pinfunction "T1OUT_14") (pintype "output"))
    )
    (net (code "37") (name "/RS232_TX2") (class "Default")
      (node (ref "P8") (pin "1") (pinfunction "1_1") (pintype "passive"))
      (node (ref "U3") (pin "13") (pinfunction "R1IN_13") (pintype "input"))
    )
    (net (code "38") (name "/RS485-A1") (class "Default")
      (node (ref "D5") (pin "1") (pinfunction "A_1") (pintype "passive"))
      (node (ref "P10") (pin "1") (pinfunction "1_1") (pintype "passive"))
      (node (ref "R133") (pin "2") (pinfunction "2_2") (pintype "passive"))
      (node (ref "R15") (pin "2") (pinfunction "2_2") (pintype "passive"))
      (node (ref "U6") (pin "6") (pinfunction "A_6") (pintype "bidirectional"))
    )
    (net (code "39") (name "/RS485-A2") (class "Default")
      (node (ref "D15") (pin "1") (pinfunction "A_1") (pintype "passive"))
      (node (ref "P11") (pin "1") (pinfunction "1_1") (pintype "passive"))
      (node (ref "R135") (pin "2") (pinfunction "2_2") (pintype "passive"))
      (node (ref "R36") (pin "2") (pinfunction "2_2") (pintype "passive"))
      (node (ref "U8") (pin "6") (pinfunction "A_6") (pintype "bidirectional"))
    )
    (net (code "40") (name "/RS485-B1") (class "Default")
      (node (ref "D14") (pin "2") (pinfunction "K_2") (pintype "passive"))
      (node (ref "P10") (pin "2") (pinfunction "2_2") (pintype "passive"))
      (node (ref "R134") (pin "1") (pinfunction "1_1") (pintype "passive"))
      (node (ref "U6") (pin "7") (pinfunction "B_7") (pintype "bidirectional"))
      (node (ref "W1") (pin "2") (pinfunction "C2_2") (pintype "passive"))
    )
    (net (code "41") (name "/RS485-B2") (class "Default")
      (node (ref "D16") (pin "2") (pinfunction "K_2") (pintype "passive"))
      (node (ref "P11") (pin "2") (pinfunction "2_2") (pintype "passive"))
      (node (ref "R136") (pin "1") (pinfunction "1_1") (pintype "passive"))
      (node (ref "U8") (pin "7") (pinfunction "B_7") (pintype "bidirectional"))
      (node (ref "W2") (pin "2") (pinfunction "C2_2") (pintype "passive"))
    )
    (net (code "42") (name "/RUN1") (class "Default")
      (node (ref "P4") (pin "1") (pinfunction "1_1") (pintype "passive"))
      (node (ref "Q3") (pin "2") (pinfunction "D_2") (pintype "passive"))
      (node (ref "Q8") (pin "2") (pinfunction "D_2") (pintype "passive"))
    )
    (net (code "43") (name "/RUN1_OUT") (class "Default")
      (node (ref "U5") (pin "15") (pinfunction "PA1/TIM2_CH2_15") (pintype "bidirectional"))
      (node (ref "U7") (pin "2") (pinfunction "K_2") (pintype "passive"))
      (node (ref "U7") (pin "4") (pinfunction "K_4") (pintype "passive"))
    )
    (net (code "44") (name "/RUN2") (class "Default")
      (node (ref "P4") (pin "3") (pinfunction "3_3") (pintype "passive"))
      (node (ref "Q6") (pin "2") (pinfunction "D_2") (pintype "passive"))
      (node (ref "Q9") (pin "2") (pinfunction "D_2") (pintype "passive"))
    )
    (net (code "45") (name "/RUN2_OUT") (class "Default")
      (node (ref "U11") (pin "6") (pinfunction "K_6") (pintype "passive"))
      (node (ref "U11") (pin "8") (pinfunction "K_8") (pintype "passive"))
      (node (ref "U5") (pin "21") (pinfunction "PA5_21") (pintype "bidirectional"))
    )
    (net (code "46") (name "/Right-Opposite") (class "Default")
      (node (ref "R131") (pin "2") (pinfunction "2_2") (pintype "passive"))
      (node (ref "U17") (pin "13") (pinfunction "E_13") (pintype "passive"))
      (node (ref "U5") (pin "38") (pinfunction "PC7_38") (pintype "bidirectional"))
    )
    (net (code "47") (name "/Right-OppositeSensor") (class "Default")
      (node (ref "LED23") (pin "2") (pinfunction "K_2") (pintype "passive"))
      (node (ref "P13") (pin "5") (pinfunction "5_5") (pintype "passive"))
      (node (ref "U17") (pin "4") (pinfunction "K_4") (pintype "passive"))
    )
    (net (code "48") (name "/RightGate-A") (class "Default")
      (node (ref "U15") (pin "2") (pinfunction "K_2") (pintype "passive"))
      (node (ref "U15") (pin "4") (pinfunction "K_4") (pintype "passive"))
      (node (ref "U5") (pin "27") (pinfunction "PB1/TIM3_CH4_27") (pintype "bidirectional"))
    )
    (net (code "49") (name "/RightGate-B") (class "Default")
      (node (ref "U15") (pin "6") (pinfunction "K_6") (pintype "passive"))
      (node (ref "U15") (pin "8") (pinfunction "K_8") (pintype "passive"))
      (node (ref "U5") (pin "33") (pinfunction "PB12/TIM1_BKIN_33") (pintype "bidirectional"))
    )
    (net (code "50") (name "/RightS-CLOSE") (class "Default")
      (node (ref "R62") (pin "2") (pinfunction "2_2") (pintype "passive"))
      (node (ref "U17") (pin "15") (pinfunction "E_15") (pintype "passive"))
      (node (ref "U5") (pin "37") (pinfunction "PC6_37") (pintype "bidirectional"))
    )
    (net (code "51") (name "/RightS-OPEN") (class "Default")
      (node (ref "R65") (pin "2") (pinfunction "2_2") (pintype "passive"))
      (node (ref "U16") (pin "9") (pinfunction "E_9") (pintype "passive"))
      (node (ref "U5") (pin "25") (pinfunction "PC5_25") (pintype "bidirectional"))
    )
    (net (code "52") (name "/RightSensor-CLOSE") (class "Default")
      (node (ref "LED6") (pin "2") (pinfunction "K_2") (pintype "passive"))
      (node (ref "P13") (pin "7") (pinfunction "7_7") (pintype "passive"))
      (node (ref "U17") (pin "2") (pinfunction "K_2") (pintype "passive"))
    )
    (net (code "53") (name "/RightSensor-OPEN") (class "Default")
      (node (ref "LED7") (pin "2") (pinfunction "K_2") (pintype "passive"))
      (node (ref "P13") (pin "6") (pinfunction "6_6") (pintype "passive"))
      (node (ref "U16") (pin "8") (pinfunction "K_8") (pintype "passive"))
    )
    (net (code "54") (name "/SCK") (class "Default")
      (node (ref "P6") (pin "3") (pinfunction "3_3") (pintype "passive"))
      (node (ref "R9") (pin "2") (pinfunction "2_2") (pintype "passive"))
      (node (ref "U5") (pin "59") (pinfunction "PB7/I2C1_SCL/TIM4_CH2_59") (pintype "bidirectional"))
    )
    (net (code "55") (name "/Spare1_24V{slash}3A") (class "Default")
      (node (ref "U13") (pin "2") (pinfunction "K_2") (pintype "passive"))
      (node (ref "U13") (pin "4") (pinfunction "K_4") (pintype "passive"))
      (node (ref "U5") (pin "36") (pinfunction "PB15/TIM1_CH3N_36") (pintype "bidirectional"))
    )
    (net (code "56") (name "/Spare1_24V{slash}3A_OUT") (class "Default")
      (node (ref "P7") (pin "7") (pinfunction "7_7") (pintype "passive"))
      (node (ref "Q11") (pin "2") (pinfunction "D_2") (pintype "passive"))
      (node (ref "Q13") (pin "2") (pinfunction "D_2") (pintype "passive"))
    )
    (net (code "57") (name "/Spare2_24V{slash}3A") (class "Default")
      (node (ref "U13") (pin "6") (pinfunction "K_6") (pintype "passive"))
      (node (ref "U13") (pin "8") (pinfunction "K_8") (pintype "passive"))
      (node (ref "U5") (pin "35") (pinfunction "PB14/TIM1_CH2N_35") (pintype "bidirectional"))
    )
    (net (code "58") (name "/Spare2_24V{slash}3A_OUT") (class "Default")
      (node (ref "P7") (pin "8") (pinfunction "8_8") (pintype "passive"))
      (node (ref "Q12") (pin "2") (pinfunction "D_2") (pintype "passive"))
      (node (ref "Q14") (pin "2") (pinfunction "D_2") (pintype "passive"))
    )
    (net (code "59") (name "/Spare3_24V{slash}3A") (class "Default")
      (node (ref "U19") (pin "6") (pinfunction "K_6") (pintype "passive"))
      (node (ref "U19") (pin "8") (pinfunction "K_8") (pintype "passive"))
      (node (ref "U5") (pin "34") (pinfunction "PB13/TIM1_CH1N_34") (pintype "bidirectional"))
    )
    (net (code "60") (name "/Spare3_24V{slash}3A_OUT") (class "Default")
      (node (ref "P7") (pin "9") (pinfunction "9_9") (pintype "passive"))
      (node (ref "Q23") (pin "2") (pinfunction "D_2") (pintype "passive"))
      (node (ref "Q25") (pin "2") (pinfunction "D_2") (pintype "passive"))
    )
    (net (code "61") (name "/Spare4_24V{slash}3A") (class "Default")
      (node (ref "U19") (pin "2") (pinfunction "K_2") (pintype "passive"))
      (node (ref "U19") (pin "4") (pinfunction "K_4") (pintype "passive"))
      (node (ref "U5") (pin "8") (pinfunction "PC0_8") (pintype "bidirectional"))
    )
    (net (code "62") (name "/Spare4_24V{slash}3A_OUT") (class "Default")
      (node (ref "P7") (pin "10") (pinfunction "10_10") (pintype "passive"))
      (node (ref "Q24") (pin "2") (pinfunction "D_2") (pintype "passive"))
      (node (ref "Q26") (pin "2") (pinfunction "D_2") (pintype "passive"))
    )
    (net (code "63") (name "/TCK{slash}SWCLK") (class "Default")
      (node (ref "JP1") (pin "2") (pinfunction "2_2") (pintype "passive"))
      (node (ref "U5") (pin "49") (pinfunction "PA14/JTCK/SWCLK_49") (pintype "bidirectional"))
    )
    (net (code "64") (name "/TMS{slash}SWDIO") (class "Default")
      (node (ref "JP1") (pin "3") (pinfunction "3_3") (pintype "passive"))
      (node (ref "U5") (pin "46") (pinfunction "PA13/JTMS/SWDIO_46") (pintype "bidirectional"))
    )
    (net (code "65") (name "/USART1_RX") (class "Default")
      (node (ref "LED3") (pin "2") (pinfunction "K_2") (pintype "passive"))
      (node (ref "U4") (pin "9") (pinfunction "TXD_9") (pintype "passive"))
      (node (ref "U5") (pin "43") (pinfunction "PA10/USART1_RX/TIM1_CH3_43") (pintype "bidirectional"))
    )
    (net (code "66") (name "/USART1_TX") (class "Default")
      (node (ref "LED2") (pin "2") (pinfunction "K_2") (pintype "passive"))
      (node (ref "U4") (pin "8") (pinfunction "RXD_8") (pintype "passive"))
      (node (ref "U5") (pin "42") (pinfunction "PA9/USART1_TX/TIM1_CH2_42") (pintype "bidirectional"))
    )
    (net (code "67") (name "/USART2_RX") (class "Default")
      (node (ref "D3") (pin "2") (pinfunction "K_2") (pintype "passive"))
      (node (ref "U3") (pin "12") (pinfunction "R1OUT_12") (pintype "output"))
      (node (ref "U5") (pin "17") (pinfunction "PA3/USART2_RX/TIM2_CH4_17") (pintype "bidirectional"))
    )
    (net (code "68") (name "/USART2_TX") (class "Default")
      (node (ref "D2") (pin "2") (pinfunction "K_2") (pintype "passive"))
      (node (ref "U3") (pin "11") (pinfunction "T1IN_11") (pintype "input"))
      (node (ref "U5") (pin "16") (pinfunction "PA2/USART2_TX/TIM2_CH3_16") (pintype "bidirectional"))
    )
    (net (code "69") (name "/USART3_RX") (class "Default")
      (node (ref "LED19") (pin "2") (pinfunction "K_2") (pintype "passive"))
      (node (ref "R30") (pin "2") (pinfunction "2_2") (pintype "passive"))
      (node (ref "U5") (pin "30") (pinfunction "PB11/USART3_RX_30") (pintype "bidirectional"))
    )
    (net (code "70") (name "/USART3_TX") (class "Default")
      (node (ref "LED18") (pin "2") (pinfunction "K_2") (pintype "passive"))
      (node (ref "R31") (pin "1") (pinfunction "1_1") (pintype "passive"))
      (node (ref "U5") (pin "29") (pinfunction "PB10/USART3_TX_29") (pintype "bidirectional"))
    )
    (net (code "71") (name "/USART4_RX") (class "Default")
      (node (ref "LED13") (pin "2") (pinfunction "K_2") (pintype "passive"))
      (node (ref "R32") (pin "2") (pinfunction "2_2") (pintype "passive"))
      (node (ref "U5") (pin "52") (pinfunction "PC11/U4_RX/SDIO_D3_52") (pintype "bidirectional"))
    )
    (net (code "72") (name "/USART4_TX") (class "Default")
      (node (ref "LED12") (pin "2") (pinfunction "K_2") (pintype "passive"))
      (node (ref "R33") (pin "1") (pinfunction "1_1") (pintype "passive"))
      (node (ref "U5") (pin "51") (pinfunction "PC10/U4_TX/SDIO_D2_51") (pintype "bidirectional"))
    )
    (net (code "73") (name "/Vibration sensor1") (class "Default")
      (node (ref "C29") (pin "1") (pinfunction "1_1") (pintype "passive"))
      (node (ref "P5") (pin "2") (pinfunction "2_2") (pintype "passive"))
      (node (ref "R73") (pin "2") (pinfunction "2_2") (pintype "passive"))
      (node (ref "U10") (pin "3") (pinfunction "1IN+_3") (pintype "passive"))
    )
    (net (code "74") (name "/Vibration sensor2") (class "Default")
      (node (ref "C34") (pin "1") (pinfunction "1_1") (pintype "passive"))
      (node (ref "P5") (pin "3") (pinfunction "3_3") (pintype "passive"))
      (node (ref "R140") (pin "2") (pinfunction "2_2") (pintype "passive"))
      (node (ref "U10") (pin "5") (pinfunction "2IN+_5") (pintype "passive"))
    )
    (net (code "75") (name "/Vibration1_IN_MCU") (class "Default")
      (node (ref "C30") (pin "2") (pinfunction "2_2") (pintype "passive"))
      (node (ref "R139") (pin "1") (pinfunction "1_1") (pintype "passive"))
      (node (ref "U10") (pin "1") (pinfunction "1OUT_1") (pintype "passive"))
      (node (ref "U5") (pin "39") (pinfunction "PC8_39") (pintype "bidirectional"))
    )
    (net (code "76") (name "/Vibration2_IN_MCU") (class "Default")
      (node (ref "C35") (pin "2") (pinfunction "2_2") (pintype "passive"))
      (node (ref "R141") (pin "1") (pinfunction "1_1") (pintype "passive"))
      (node (ref "U10") (pin "7") (pinfunction "2OUT_7") (pintype "passive"))
      (node (ref "U5") (pin "40") (pinfunction "PC9_40") (pintype "bidirectional"))
    )
    (net (code "78") (name "24V0") (class "Default")
      (node (ref "C2") (pin "2") (pinfunction "2_2") (pintype "passive"))
      (node (ref "C24") (pin "1") (pinfunction "1_1") (pintype "passive"))
      (node (ref "C25") (pin "1") (pinfunction "1_1") (pintype "passive"))
      (node (ref "C26") (pin "1") (pinfunction "1_1") (pintype "passive"))
      (node (ref "C27") (pin "1") (pinfunction "1_1") (pintype "passive"))
      (node (ref "C3") (pin "1") (pinfunction "1_1") (pintype "passive"))
      (node (ref "C36") (pin "2") (pinfunction "2_2") (pintype "passive"))
      (node (ref "D1") (pin "1") (pinfunction "A_1") (pintype "passive"))
      (node (ref "D11") (pin "1") (pinfunction "A_1") (pintype "passive"))
      (node (ref "D13") (pin "1") (pinfunction "A_1") (pintype "passive"))
      (node (ref "D7") (pin "1") (pinfunction "A_1") (pintype "passive"))
      (node (ref "D9") (pin "1") (pinfunction "A_1") (pintype "passive"))
      (node (ref "LED10") (pin "2") (pinfunction "K_2") (pintype "passive"))
      (node (ref "LED21") (pin "2") (pinfunction "K_2") (pintype "passive"))
      (node (ref "P1") (pin "2") (pinfunction "2_2") (pintype "passive"))
      (node (ref "P10") (pin "5") (pinfunction "5_5") (pintype "passive"))
      (node (ref "P10") (pin "6") (pinfunction "6_6") (pintype "passive"))
      (node (ref "P11") (pin "5") (pinfunction "5_5") (pintype "passive"))
      (node (ref "P11") (pin "6") (pinfunction "6_6") (pintype "passive"))
      (node (ref "P12") (pin "2") (pinfunction "2_2") (pintype "passive"))
      (node (ref "P13") (pin "2") (pinfunction "2_2") (pintype "passive"))
      (node (ref "P2") (pin "2") (pinfunction "2_2") (pintype "passive"))
      (node (ref "P3") (pin "2") (pinfunction "2_2") (pintype "passive"))
      (node (ref "P7") (pin "2") (pinfunction "2_2") (pintype "passive"))
      (node (ref "PT1") (pin "1") (pinfunction "1_1") (pintype "passive"))
      (node (ref "PT2") (pin "1") (pinfunction "1_1") (pintype "passive"))
      (node (ref "Q11") (pin "3") (pinfunction "S_3") (pintype "passive"))
      (node (ref "Q12") (pin "3") (pinfunction "S_3") (pintype "passive"))
      (node (ref "Q15") (pin "3") (pinfunction "S_3") (pintype "passive"))
      (node (ref "Q16") (pin "3") (pinfunction "S_3") (pintype "passive"))
      (node (ref "Q20") (pin "3") (pinfunction "S_3") (pintype "passive"))
      (node (ref "Q22") (pin "3") (pinfunction "S_3") (pintype "passive"))
      (node (ref "Q23") (pin "3") (pinfunction "S_3") (pintype "passive"))
      (node (ref "Q24") (pin "3") (pinfunction "S_3") (pintype "passive"))
      (node (ref "Q3") (pin "3") (pinfunction "S_3") (pintype "passive"))
      (node (ref "Q4") (pin "3") (pinfunction "S_3") (pintype "passive"))
      (node (ref "Q6") (pin "3") (pinfunction "S_3") (pintype "passive"))
      (node (ref "Q7") (pin "3") (pinfunction "S_3") (pintype "passive"))
      (node (ref "R100") (pin "1") (pinfunction "1_1") (pintype "passive"))
      (node (ref "R111") (pin "1") (pinfunction "1_1") (pintype "passive"))
      (node (ref "R112") (pin "1") (pinfunction "1_1") (pintype "passive"))
      (node (ref "R113") (pin "1") (pinfunction "1_1") (pintype "passive"))
      (node (ref "R114") (pin "1") (pinfunction "1_1") (pintype "passive"))
      (node (ref "R115") (pin "1") (pinfunction "1_1") (pintype "passive"))
      (node (ref "R116") (pin "1") (pinfunction "1_1") (pintype "passive"))
      (node (ref "R121") (pin "1") (pinfunction "1_1") (pintype "passive"))
      (node (ref "R122") (pin "1") (pinfunction "1_1") (pintype "passive"))
      (node (ref "R20") (pin "1") (pinfunction "1_1") (pintype "passive"))
      (node (ref "R21") (pin "1") (pinfunction "1_1") (pintype "passive"))
      (node (ref "R22") (pin "1") (pinfunction "1_1") (pintype "passive"))
      (node (ref "R23") (pin "1") (pinfunction "1_1") (pintype "passive"))
      (node (ref "R53") (pin "1") (pinfunction "1_1") (pintype "passive"))
      (node (ref "R54") (pin "1") (pinfunction "1_1") (pintype "passive"))
      (node (ref "R59") (pin "1") (pinfunction "1_1") (pintype "passive"))
      (node (ref "R72") (pin "1") (pinfunction "1_1") (pintype "passive"))
      (node (ref "R81") (pin "1") (pinfunction "1_1") (pintype "passive"))
      (node (ref "R84") (pin "1") (pinfunction "1_1") (pintype "passive"))
      (node (ref "R86") (pin "1") (pinfunction "1_1") (pintype "passive"))
      (node (ref "R88") (pin "1") (pinfunction "1_1") (pintype "passive"))
      (node (ref "R94") (pin "1") (pinfunction "1_1") (pintype "passive"))
      (node (ref "R98") (pin "1") (pinfunction "1_1") (pintype "passive"))
      (node (ref "R99") (pin "1") (pinfunction "1_1") (pintype "passive"))
      (node (ref "U1") (pin "1") (pinfunction "GND_1") (pintype "passive"))
      (node (ref "U11") (pin "13") (pinfunction "E_13") (pintype "passive"))
      (node (ref "U11") (pin "9") (pinfunction "E_9") (pintype "passive"))
      (node (ref "U13") (pin "13") (pinfunction "E_13") (pintype "passive"))
      (node (ref "U13") (pin "9") (pinfunction "E_9") (pintype "passive"))
      (node (ref "U14") (pin "13") (pinfunction "E_13") (pintype "passive"))
      (node (ref "U14") (pin "9") (pinfunction "E_9") (pintype "passive"))
      (node (ref "U15") (pin "13") (pinfunction "E_13") (pintype "passive"))
      (node (ref "U15") (pin "9") (pinfunction "E_9") (pintype "passive"))
      (node (ref "U19") (pin "13") (pinfunction "E_13") (pintype "passive"))
      (node (ref "U19") (pin "9") (pinfunction "E_9") (pintype "passive"))
      (node (ref "U7") (pin "13") (pinfunction "E_13") (pintype "passive"))
      (node (ref "U7") (pin "9") (pinfunction "E_9") (pintype "passive"))
      (node (ref "U9") (pin "6") (pinfunction "K_6") (pintype "passive"))
      (node (ref "U9") (pin "8") (pinfunction "K_8") (pintype "passive"))
    )
    (net (code "79") (name "GND") (class "Default")
      (node (ref "BUTTON1") (pin "3") (pinfunction "3_3") (pintype "passive"))
      (node (ref "BUTTON1") (pin "4") (pinfunction "4_4") (pintype "passive"))
      (node (ref "C1") (pin "1") (pinfunction "1_1") (pintype "passive"))
      (node (ref "C10") (pin "2") (pinfunction "2_2") (pintype "passive"))
      (node (ref "C13") (pin "2") (pinfunction "2_2") (pintype "passive"))
      (node (ref "C14") (pin "1") (pinfunction "1_1") (pintype "passive"))
      (node (ref "C15") (pin "1") (pinfunction "1_1") (pintype "passive"))
      (node (ref "C16") (pin "1") (pinfunction "1_1") (pintype "passive"))
      (node (ref "C17") (pin "1") (pinfunction "1_1") (pintype "passive"))
      (node (ref "C18") (pin "1") (pinfunction "1_1") (pintype "passive"))
      (node (ref "C19") (pin "1") (pinfunction "1_1") (pintype "passive"))
      (node (ref "C20") (pin "1") (pinfunction "1_1") (pintype "passive"))
      (node (ref "C21") (pin "1") (pinfunction "1_1") (pintype "passive"))
      (node (ref "C22") (pin "1") (pinfunction "1_1") (pintype "passive"))
      (node (ref "C23") (pin "2") (pinfunction "2_2") (pintype "passive"))
      (node (ref "C28") (pin "2") (pinfunction "2_2") (pintype "passive"))
      (node (ref "C29") (pin "2") (pinfunction "2_2") (pintype "passive"))
      (node (ref "C30") (pin "1") (pinfunction "1_1") (pintype "passive"))
      (node (ref "C33") (pin "1") (pinfunction "1_1") (pintype "passive"))
      (node (ref "C34") (pin "2") (pinfunction "2_2") (pintype "passive"))
      (node (ref "C35") (pin "1") (pinfunction "1_1") (pintype "passive"))
      (node (ref "C4") (pin "2") (pinfunction "2_2") (pintype "passive"))
      (node (ref "C5") (pin "1") (pinfunction "1_1") (pintype "passive"))
      (node (ref "C6") (pin "2") (pinfunction "2_2") (pintype "passive"))
      (node (ref "C7") (pin "1") (pinfunction "1_1") (pintype "passive"))
      (node (ref "C8") (pin "2") (pinfunction "2_2") (pintype "passive"))
      (node (ref "C9") (pin "2") (pinfunction "2_2") (pintype "passive"))
      (node (ref "CB1") (pin "1") (pinfunction "1_1") (pintype "passive"))
      (node (ref "D14") (pin "1") (pinfunction "A_1") (pintype "passive"))
      (node (ref "D15") (pin "2") (pinfunction "K_2") (pintype "passive"))
      (node (ref "D16") (pin "1") (pinfunction "A_1") (pintype "passive"))
      (node (ref "D5") (pin "2") (pinfunction "K_2") (pintype "passive"))
      (node (ref "JP1") (pin "4") (pinfunction "4_4") (pintype "passive"))
      (node (ref "LED1") (pin "2") (pinfunction "2_2") (pintype "passive"))
      (node (ref "P5") (pin "4") (pinfunction "4_4") (pintype "passive"))
      (node (ref "P6") (pin "4") (pinfunction "4_4") (pintype "passive"))
      (node (ref "P8") (pin "2") (pinfunction "2_2") (pintype "passive"))
      (node (ref "PT3") (pin "1") (pinfunction "1_1") (pintype "passive"))
      (node (ref "PT4") (pin "1") (pinfunction "1_1") (pintype "passive"))
      (node (ref "Q1") (pin "2") (pinfunction "E_2") (pintype "passive"))
      (node (ref "Q2") (pin "2") (pinfunction "E_2") (pintype "passive"))
      (node (ref "R131") (pin "1") (pinfunction "1_1") (pintype "passive"))
      (node (ref "R132") (pin "1") (pinfunction "1_1") (pintype "passive"))
      (node (ref "R134") (pin "2") (pinfunction "2_2") (pintype "passive"))
      (node (ref "R136") (pin "2") (pinfunction "2_2") (pintype "passive"))
      (node (ref "R137") (pin "2") (pinfunction "2_2") (pintype "passive"))
      (node (ref "R48") (pin "1") (pinfunction "1_1") (pintype "passive"))
      (node (ref "R49") (pin "1") (pinfunction "1_1") (pintype "passive"))
      (node (ref "R50") (pin "1") (pinfunction "1_1") (pintype "passive"))
      (node (ref "R51") (pin "1") (pinfunction "1_1") (pintype "passive"))
      (node (ref "R62") (pin "1") (pinfunction "1_1") (pintype "passive"))
      (node (ref "R65") (pin "1") (pinfunction "1_1") (pintype "passive"))
      (node (ref "R68") (pin "1") (pinfunction "1_1") (pintype "passive"))
      (node (ref "R7") (pin "1") (pinfunction "1_1") (pintype "passive"))
      (node (ref "R71") (pin "1") (pinfunction "1_1") (pintype "passive"))
      (node (ref "R80") (pin "1") (pinfunction "1_1") (pintype "passive"))
      (node (ref "U1") (pin "4") (pinfunction "0V_4") (pintype "passive"))
      (node (ref "U10") (pin "4") (pinfunction "GND_4") (pintype "passive"))
      (node (ref "U2") (pin "1") (pinfunction "GND_1") (pintype "passive"))
      (node (ref "U3") (pin "15") (pinfunction "GND_15") (pintype "power_in"))
      (node (ref "U4") (pin "10") (pinfunction "GND_10") (pintype "passive"))
      (node (ref "U5") (pin "12") (pinfunction "VSSA_12") (pintype "power_in"))
      (node (ref "U5") (pin "18") (pinfunction "VSS_4_18") (pintype "power_in"))
      (node (ref "U5") (pin "31") (pinfunction "VSS_1_31") (pintype "power_in"))
      (node (ref "U5") (pin "47") (pinfunction "VSS_2_47") (pintype "power_in"))
      (node (ref "U5") (pin "63") (pinfunction "VSS_3_63") (pintype "power_in"))
      (node (ref "U6") (pin "4") (pinfunction "DI_4") (pintype "input"))
      (node (ref "U6") (pin "5") (pinfunction "GND_5") (pintype "power_in"))
      (node (ref "U8") (pin "4") (pinfunction "DI_4") (pintype "input"))
      (node (ref "U8") (pin "5") (pinfunction "GND_5") (pintype "power_in"))
    )
    (net (code "80") (name "Net-(D2-A)") (class "Default")
      (node (ref "D2") (pin "1") (pinfunction "A_1") (pintype "passive"))
      (node (ref "R2") (pin "2") (pinfunction "2_2") (pintype "passive"))
    )
    (net (code "81") (name "Net-(D3-A)") (class "Default")
      (node (ref "D3") (pin "1") (pinfunction "A_1") (pintype "passive"))
      (node (ref "R3") (pin "2") (pinfunction "2_2") (pintype "passive"))
    )
    (net (code "82") (name "Net-(D4-K)") (class "Default")
      (node (ref "D4") (pin "2") (pinfunction "K_2") (pintype "passive"))
      (node (ref "U5") (pin "1") (pinfunction "VBAT_1") (pintype "power_in"))
    )
    (net (code "83") (name "Net-(D6-K)") (class "Default")
      (node (ref "D6") (pin "2") (pinfunction "K_2") (pintype "passive"))
      (node (ref "D8") (pin "2") (pinfunction "K_2") (pintype "passive"))
      (node (ref "F3") (pin "1") (pinfunction "1_1") (pintype "passive"))
      (node (ref "Q17") (pin "3") (pinfunction "S_3") (pintype "passive"))
      (node (ref "Q19") (pin "3") (pinfunction "S_3") (pintype "passive"))
    )
    (net (code "84") (name "Net-(D10-K)") (class "Default")
      (node (ref "D10") (pin "2") (pinfunction "K_2") (pintype "passive"))
      (node (ref "D12") (pin "2") (pinfunction "K_2") (pintype "passive"))
      (node (ref "F4") (pin "1") (pinfunction "1_1") (pintype "passive"))
      (node (ref "Q18") (pin "3") (pinfunction "S_3") (pintype "passive"))
      (node (ref "Q21") (pin "3") (pinfunction "S_3") (pintype "passive"))
    )
    (net (code "85") (name "Net-(LED1-Pad1)") (class "Default")
      (node (ref "LED1") (pin "1") (pinfunction "1_1") (pintype "passive"))
      (node (ref "R1") (pin "2") (pinfunction "2_2") (pintype "passive"))
    )
    (net (code "86") (name "Net-(LED2-A)") (class "Default")
      (node (ref "LED2") (pin "1") (pinfunction "A_1") (pintype "passive"))
      (node (ref "R4") (pin "2") (pinfunction "2_2") (pintype "passive"))
    )
    (net (code "87") (name "Net-(LED3-A)") (class "Default")
      (node (ref "LED3") (pin "1") (pinfunction "A_1") (pintype "passive"))
      (node (ref "R5") (pin "2") (pinfunction "2_2") (pintype "passive"))
    )
    (net (code "88") (name "Net-(LED4-A)") (class "Default")
      (node (ref "LED4") (pin "1") (pinfunction "A_1") (pintype "passive"))
      (node (ref "R11") (pin "2") (pinfunction "2_2") (pintype "passive"))
    )
    (net (code "89") (name "Net-(LED4-K)") (class "Default")
      (node (ref "LED4") (pin "2") (pinfunction "K_2") (pintype "passive"))
      (node (ref "U5") (pin "57") (pinfunction "PB5_57") (pintype "bidirectional"))
    )
    (net (code "90") (name "Net-(LED5-Pad1)") (class "Default")
      (node (ref "LED5") (pin "1") (pinfunction "1_1") (pintype "passive"))
      (node (ref "R10") (pin "2") (pinfunction "2_2") (pintype "passive"))
    )
    (net (code "91") (name "Net-(LED6-A)") (class "Default")
      (node (ref "LED6") (pin "1") (pinfunction "A_1") (pintype "passive"))
      (node (ref "R60") (pin "2") (pinfunction "2_2") (pintype "passive"))
    )
    (net (code "92") (name "Net-(LED7-A)") (class "Default")
      (node (ref "LED7") (pin "1") (pinfunction "A_1") (pintype "passive"))
      (node (ref "R63") (pin "2") (pinfunction "2_2") (pintype "passive"))
    )
    (net (code "93") (name "Net-(LED8-A)") (class "Default")
      (node (ref "LED8") (pin "1") (pinfunction "A_1") (pintype "passive"))
      (node (ref "R66") (pin "2") (pinfunction "2_2") (pintype "passive"))
    )
    (net (code "94") (name "Net-(LED9-A)") (class "Default")
      (node (ref "LED9") (pin "1") (pinfunction "A_1") (pintype "passive"))
      (node (ref "R69") (pin "2") (pinfunction "2_2") (pintype "passive"))
    )
    (net (code "95") (name "Net-(LED10-A)") (class "Default")
      (node (ref "LED10") (pin "1") (pinfunction "A_1") (pintype "passive"))
      (node (ref "R41") (pin "2") (pinfunction "2_2") (pintype "passive"))
    )
    (net (code "96") (name "Net-(LED11-A)") (class "Default")
      (node (ref "LED11") (pin "1") (pinfunction "A_1") (pintype "passive"))
      (node (ref "R43") (pin "2") (pinfunction "2_2") (pintype "passive"))
    )
    (net (code "97") (name "Net-(LED12-A)") (class "Default")
      (node (ref "LED12") (pin "1") (pinfunction "A_1") (pintype "passive"))
      (node (ref "R28") (pin "2") (pinfunction "2_2") (pintype "passive"))
    )
    (net (code "98") (name "Net-(LED13-A)") (class "Default")
      (node (ref "LED13") (pin "1") (pinfunction "A_1") (pintype "passive"))
      (node (ref "R29") (pin "2") (pinfunction "2_2") (pintype "passive"))
    )
    (net (code "99") (name "Net-(LED14-A)") (class "Default")
      (node (ref "LED14") (pin "1") (pinfunction "A_1") (pintype "passive"))
      (node (ref "LED16") (pin "2") (pinfunction "K_2") (pintype "passive"))
      (node (ref "R101") (pin "2") (pinfunction "2_2") (pintype "passive"))
    )
    (net (code "100") (name "Net-(LED15-A)") (class "Default")
      (node (ref "LED15") (pin "1") (pinfunction "A_1") (pintype "passive"))
      (node (ref "LED17") (pin "2") (pinfunction "K_2") (pintype "passive"))
      (node (ref "R102") (pin "2") (pinfunction "2_2") (pintype "passive"))
    )
    (net (code "101") (name "Net-(LED18-A)") (class "Default")
      (node (ref "LED18") (pin "1") (pinfunction "A_1") (pintype "passive"))
      (node (ref "R13") (pin "2") (pinfunction "2_2") (pintype "passive"))
    )
    (net (code "102") (name "Net-(LED19-A)") (class "Default")
      (node (ref "LED19") (pin "1") (pinfunction "A_1") (pintype "passive"))
      (node (ref "R14") (pin "2") (pinfunction "2_2") (pintype "passive"))
    )
    (net (code "103") (name "Net-(LED20-A)") (class "Default")
      (node (ref "LED20") (pin "1") (pinfunction "A_1") (pintype "passive"))
      (node (ref "R42") (pin "2") (pinfunction "2_2") (pintype "passive"))
    )
    (net (code "104") (name "Net-(LED21-A)") (class "Default")
      (node (ref "LED21") (pin "1") (pinfunction "A_1") (pintype "passive"))
      (node (ref "R40") (pin "2") (pinfunction "2_2") (pintype "passive"))
    )
    (net (code "105") (name "Net-(LED22-A)") (class "Default")
      (node (ref "LED22") (pin "1") (pinfunction "A_1") (pintype "passive"))
      (node (ref "R78") (pin "2") (pinfunction "2_2") (pintype "passive"))
    )
    (net (code "106") (name "Net-(LED23-A)") (class "Default")
      (node (ref "LED23") (pin "1") (pinfunction "A_1") (pintype "passive"))
      (node (ref "R127") (pin "2") (pinfunction "2_2") (pintype "passive"))
    )
    (net (code "107") (name "Net-(LED24-A)") (class "Default")
      (node (ref "LED24") (pin "1") (pinfunction "A_1") (pintype "passive"))
      (node (ref "R128") (pin "2") (pinfunction "2_2") (pintype "passive"))
    )
    (net (code "108") (name "Net-(Q1-B)") (class "Default")
      (node (ref "Q1") (pin "1") (pinfunction "B_1") (pintype "passive"))
      (node (ref "R31") (pin "2") (pinfunction "2_2") (pintype "passive"))
    )
    (net (code "109") (name "Net-(Q1-C)") (class "Default")
      (node (ref "Q1") (pin "3") (pinfunction "C_3") (pintype "passive"))
      (node (ref "R34") (pin "2") (pinfunction "2_2") (pintype "passive"))
      (node (ref "U6") (pin "2") (pinfunction "~{RE}_2") (pintype "input"))
      (node (ref "U6") (pin "3") (pinfunction "DE_3") (pintype "input"))
    )
    (net (code "110") (name "Net-(Q2-B)") (class "Default")
      (node (ref "Q2") (pin "1") (pinfunction "B_1") (pintype "passive"))
      (node (ref "R33") (pin "2") (pinfunction "2_2") (pintype "passive"))
    )
    (net (code "111") (name "Net-(Q2-C)") (class "Default")
      (node (ref "Q2") (pin "3") (pinfunction "C_3") (pintype "passive"))
      (node (ref "R35") (pin "2") (pinfunction "2_2") (pintype "passive"))
      (node (ref "U8") (pin "2") (pinfunction "~{RE}_2") (pintype "input"))
      (node (ref "U8") (pin "3") (pinfunction "DE_3") (pintype "input"))
    )
    (net (code "112") (name "Net-(Q3-G)") (class "Default")
      (node (ref "Q3") (pin "1") (pinfunction "G_1") (pintype "passive"))
      (node (ref "R21") (pin "2") (pinfunction "2_2") (pintype "passive"))
      (node (ref "R25") (pin "1") (pinfunction "1_1") (pintype "passive"))
      (node (ref "U7") (pin "14") (pinfunction "C_14") (pintype "passive"))
    )
    (net (code "113") (name "Net-(Q4-G)") (class "Default")
      (node (ref "Q4") (pin "1") (pinfunction "G_1") (pintype "passive"))
      (node (ref "R23") (pin "2") (pinfunction "2_2") (pintype "passive"))
      (node (ref "R27") (pin "1") (pinfunction "1_1") (pintype "passive"))
      (node (ref "U7") (pin "10") (pinfunction "C_10") (pintype "passive"))
    )
    (net (code "114") (name "Net-(Q5-G)") (class "Default")
      (node (ref "Q5") (pin "1") (pinfunction "G_1") (pintype "passive"))
      (node (ref "R26") (pin "1") (pinfunction "1_1") (pintype "passive"))
      (node (ref "U7") (pin "12") (pinfunction "C_12") (pintype "passive"))
    )
    (net (code "115") (name "Net-(Q6-G)") (class "Default")
      (node (ref "Q6") (pin "1") (pinfunction "G_1") (pintype "passive"))
      (node (ref "R58") (pin "1") (pinfunction "1_1") (pintype "passive"))
      (node (ref "R59") (pin "2") (pinfunction "2_2") (pintype "passive"))
      (node (ref "U11") (pin "10") (pinfunction "C_10") (pintype "passive"))
    )
    (net (code "116") (name "Net-(Q7-G)") (class "Default")
      (node (ref "Q7") (pin "1") (pinfunction "G_1") (pintype "passive"))
      (node (ref "R56") (pin "1") (pinfunction "1_1") (pintype "passive"))
      (node (ref "R72") (pin "2") (pinfunction "2_2") (pintype "passive"))
      (node (ref "U11") (pin "14") (pinfunction "C_14") (pintype "passive"))
    )
    (net (code "117") (name "Net-(Q8-G)") (class "Default")
      (node (ref "Q8") (pin "1") (pinfunction "G_1") (pintype "passive"))
      (node (ref "R24") (pin "1") (pinfunction "1_1") (pintype "passive"))
      (node (ref "U7") (pin "16") (pinfunction "C_16") (pintype "passive"))
    )
    (net (code "118") (name "Net-(Q9-G)") (class "Default")
      (node (ref "Q9") (pin "1") (pinfunction "G_1") (pintype "passive"))
      (node (ref "R57") (pin "1") (pinfunction "1_1") (pintype "passive"))
      (node (ref "U11") (pin "12") (pinfunction "C_12") (pintype "passive"))
    )
    (net (code "119") (name "Net-(Q10-G)") (class "Default")
      (node (ref "Q10") (pin "1") (pinfunction "G_1") (pintype "passive"))
      (node (ref "R55") (pin "1") (pinfunction "1_1") (pintype "passive"))
      (node (ref "U11") (pin "16") (pinfunction "C_16") (pintype "passive"))
    )
    (net (code "120") (name "Net-(Q11-G)") (class "Default")
      (node (ref "Q11") (pin "1") (pinfunction "G_1") (pintype "passive"))
      (node (ref "R83") (pin "1") (pinfunction "1_1") (pintype "passive"))
      (node (ref "R84") (pin "2") (pinfunction "2_2") (pintype "passive"))
      (node (ref "U13") (pin "14") (pinfunction "C_14") (pintype "passive"))
    )
    (net (code "121") (name "Net-(Q12-G)") (class "Default")
      (node (ref "Q12") (pin "1") (pinfunction "G_1") (pintype "passive"))
      (node (ref "R87") (pin "1") (pinfunction "1_1") (pintype "passive"))
      (node (ref "R88") (pin "2") (pinfunction "2_2") (pintype "passive"))
      (node (ref "U13") (pin "10") (pinfunction "C_10") (pintype "passive"))
    )
    (net (code "122") (name "Net-(Q13-G)") (class "Default")
      (node (ref "Q13") (pin "1") (pinfunction "G_1") (pintype "passive"))
      (node (ref "R82") (pin "1") (pinfunction "1_1") (pintype "passive"))
      (node (ref "U13") (pin "16") (pinfunction "C_16") (pintype "passive"))
    )
    (net (code "123") (name "Net-(Q14-G)") (class "Default")
      (node (ref "Q14") (pin "1") (pinfunction "G_1") (pintype "passive"))
      (node (ref "R85") (pin "1") (pinfunction "1_1") (pintype "passive"))
      (node (ref "U13") (pin "12") (pinfunction "C_12") (pintype "passive"))
    )
    (net (code "124") (name "Net-(Q15-G)") (class "Default")
      (node (ref "Q15") (pin "1") (pinfunction "G_1") (pintype "passive"))
      (node (ref "R97") (pin "1") (pinfunction "1_1") (pintype "passive"))
      (node (ref "R98") (pin "2") (pinfunction "2_2") (pintype "passive"))
      (node (ref "U14") (pin "14") (pinfunction "C_14") (pintype "passive"))
    )
    (net (code "125") (name "Net-(Q16-G)") (class "Default")
      (node (ref "Q16") (pin "1") (pinfunction "G_1") (pintype "passive"))
      (node (ref "R100") (pin "2") (pinfunction "2_2") (pintype "passive"))
      (node (ref "R96") (pin "1") (pinfunction "1_1") (pintype "passive"))
      (node (ref "U15") (pin "14") (pinfunction "C_14") (pintype "passive"))
    )
    (net (code "126") (name "Net-(Q17-G)") (class "Default")
      (node (ref "Q17") (pin "1") (pinfunction "G_1") (pintype "passive"))
      (node (ref "R93") (pin "1") (pinfunction "1_1") (pintype "passive"))
      (node (ref "U14") (pin "16") (pinfunction "C_16") (pintype "passive"))
    )
    (net (code "127") (name "Net-(Q18-G)") (class "Default")
      (node (ref "Q18") (pin "1") (pinfunction "G_1") (pintype "passive"))
      (node (ref "R95") (pin "1") (pinfunction "1_1") (pintype "passive"))
      (node (ref "U15") (pin "16") (pinfunction "C_16") (pintype "passive"))
    )
    (net (code "128") (name "Net-(Q19-G)") (class "Default")
      (node (ref "Q19") (pin "1") (pinfunction "G_1") (pintype "passive"))
      (node (ref "R107") (pin "1") (pinfunction "1_1") (pintype "passive"))
      (node (ref "U14") (pin "12") (pinfunction "C_12") (pintype "passive"))
    )
    (net (code "129") (name "Net-(Q20-G)") (class "Default")
      (node (ref "Q20") (pin "1") (pinfunction "G_1") (pintype "passive"))
      (node (ref "R108") (pin "1") (pinfunction "1_1") (pintype "passive"))
      (node (ref "R112") (pin "2") (pinfunction "2_2") (pintype "passive"))
      (node (ref "U14") (pin "10") (pinfunction "C_10") (pintype "passive"))
    )
    (net (code "130") (name "Net-(Q21-G)") (class "Default")
      (node (ref "Q21") (pin "1") (pinfunction "G_1") (pintype "passive"))
      (node (ref "R109") (pin "1") (pinfunction "1_1") (pintype "passive"))
      (node (ref "U15") (pin "12") (pinfunction "C_12") (pintype "passive"))
    )
    (net (code "131") (name "Net-(Q22-G)") (class "Default")
      (node (ref "Q22") (pin "1") (pinfunction "G_1") (pintype "passive"))
      (node (ref "R110") (pin "1") (pinfunction "1_1") (pintype "passive"))
      (node (ref "R114") (pin "2") (pinfunction "2_2") (pintype "passive"))
      (node (ref "U15") (pin "10") (pinfunction "C_10") (pintype "passive"))
    )
    (net (code "132") (name "Net-(Q23-G)") (class "Default")
      (node (ref "Q23") (pin "1") (pinfunction "G_1") (pintype "passive"))
      (node (ref "R120") (pin "1") (pinfunction "1_1") (pintype "passive"))
      (node (ref "R121") (pin "2") (pinfunction "2_2") (pintype "passive"))
      (node (ref "U19") (pin "10") (pinfunction "C_10") (pintype "passive"))
    )
    (net (code "133") (name "Net-(Q24-G)") (class "Default")
      (node (ref "Q24") (pin "1") (pinfunction "G_1") (pintype "passive"))
      (node (ref "R118") (pin "1") (pinfunction "1_1") (pintype "passive"))
      (node (ref "R122") (pin "2") (pinfunction "2_2") (pintype "passive"))
      (node (ref "U19") (pin "14") (pinfunction "C_14") (pintype "passive"))
    )
    (net (code "134") (name "Net-(Q25-G)") (class "Default")
      (node (ref "Q25") (pin "1") (pinfunction "G_1") (pintype "passive"))
      (node (ref "R119") (pin "1") (pinfunction "1_1") (pintype "passive"))
      (node (ref "U19") (pin "12") (pinfunction "C_12") (pintype "passive"))
    )
    (net (code "135") (name "Net-(Q26-G)") (class "Default")
      (node (ref "Q26") (pin "1") (pinfunction "G_1") (pintype "passive"))
      (node (ref "R117") (pin "1") (pinfunction "1_1") (pintype "passive"))
      (node (ref "U19") (pin "16") (pinfunction "C_16") (pintype "passive"))
    )
    (net (code "136") (name "Net-(U2-Vout)") (class "Default")
      (node (ref "F2") (pin "1") (pinfunction "1_1") (pintype "passive"))
      (node (ref "U2") (pin "2") (pinfunction "Vout_2") (pintype "passive"))
      (node (ref "U2") (pin "4") (pintype "passive"))
    )
    (net (code "137") (name "Net-(U3-C1+)") (class "Default")
      (node (ref "C11") (pin "2") (pinfunction "2_2") (pintype "passive"))
      (node (ref "U3") (pin "1") (pinfunction "C1+_1") (pintype "passive"))
    )
    (net (code "138") (name "Net-(U3-C1-)") (class "Default")
      (node (ref "C11") (pin "1") (pinfunction "1_1") (pintype "passive"))
      (node (ref "U3") (pin "3") (pinfunction "C1-_3") (pintype "passive"))
    )
    (net (code "139") (name "Net-(U3-C2+)") (class "Default")
      (node (ref "C12") (pin "1") (pinfunction "1_1") (pintype "passive"))
      (node (ref "U3") (pin "4") (pinfunction "C2+_4") (pintype "passive"))
    )
    (net (code "140") (name "Net-(U3-C2-)") (class "Default")
      (node (ref "C12") (pin "2") (pinfunction "2_2") (pintype "passive"))
      (node (ref "U3") (pin "5") (pinfunction "C2-_5") (pintype "passive"))
    )
    (net (code "141") (name "Net-(U3-V+)") (class "Default")
      (node (ref "C8") (pin "1") (pinfunction "1_1") (pintype "passive"))
      (node (ref "U3") (pin "2") (pinfunction "V+_2") (pintype "power_in"))
    )
    (net (code "142") (name "Net-(U3-V-)") (class "Default")
      (node (ref "C10") (pin "1") (pinfunction "1_1") (pintype "passive"))
      (node (ref "U3") (pin "6") (pinfunction "V-_6") (pintype "power_in"))
    )
    (net (code "143") (name "Net-(U4-LED_DATA-Pad13)") (class "Default")
      (node (ref "U4") (pin "13") (pinfunction "LED_DATA_13") (pintype "passive"))
      (node (ref "U4") (pin "7") (pinfunction "LED_DATA_7") (pintype "passive"))
    )
    (net (code "144") (name "Net-(U4-LED_LINK-Pad12)") (class "Default")
      (node (ref "U4") (pin "12") (pinfunction "LED_LINK_12") (pintype "passive"))
      (node (ref "U4") (pin "16") (pinfunction "LED_LINK_16") (pintype "passive"))
    )
    (net (code "145") (name "Net-(U4-Reload(CFG))") (class "Default")
      (node (ref "CB1") (pin "2") (pinfunction "2_2") (pintype "passive"))
      (node (ref "U4") (pin "6") (pinfunction "Reload(CFG)_6") (pintype "passive"))
    )
    (net (code "146") (name "Net-(U5-BOOT0)") (class "Default")
      (node (ref "R7") (pin "2") (pinfunction "2_2") (pintype "passive"))
      (node (ref "U5") (pin "60") (pinfunction "BOOT0_60") (pintype "input"))
    )
    (net (code "147") (name "Net-(U5-PC1)") (class "Default")
      (node (ref "LED5") (pin "2") (pinfunction "2_2") (pintype "passive"))
      (node (ref "U5") (pin "9") (pinfunction "PC1_9") (pintype "bidirectional"))
    )
    (net (code "148") (name "Net-(U5-PC2)") (class "Default")
      (node (ref "BUTTON1") (pin "1") (pintype "passive"))
      (node (ref "BUTTON1") (pin "2") (pintype "passive"))
      (node (ref "U5") (pin "10") (pinfunction "PC2_10") (pintype "bidirectional"))
    )
    (net (code "149") (name "Net-(U6-RO)") (class "Default")
      (node (ref "R30") (pin "1") (pinfunction "1_1") (pintype "passive"))
      (node (ref "U6") (pin "1") (pinfunction "RO_1") (pintype "output"))
    )
    (net (code "150") (name "Net-(U7A-A)") (class "Default")
      (node (ref "R16") (pin "1") (pinfunction "1_1") (pintype "passive"))
      (node (ref "U7") (pin "1") (pinfunction "A_1") (pintype "passive"))
    )
    (net (code "151") (name "Net-(U7A-E)") (class "Default")
      (node (ref "R20") (pin "2") (pinfunction "2_2") (pintype "passive"))
      (node (ref "U7") (pin "15") (pinfunction "E_15") (pintype "passive"))
    )
    (net (code "152") (name "Net-(U7B-A)") (class "Default")
      (node (ref "R17") (pin "2") (pinfunction "2_2") (pintype "passive"))
      (node (ref "U7") (pin "3") (pinfunction "A_3") (pintype "passive"))
    )
    (net (code "153") (name "Net-(U7C-A)") (class "Default")
      (node (ref "R18") (pin "2") (pinfunction "2_2") (pintype "passive"))
      (node (ref "U7") (pin "5") (pinfunction "A_5") (pintype "passive"))
    )
    (net (code "154") (name "Net-(U7C-E)") (class "Default")
      (node (ref "R22") (pin "2") (pinfunction "2_2") (pintype "passive"))
      (node (ref "U7") (pin "11") (pinfunction "E_11") (pintype "passive"))
    )
    (net (code "155") (name "Net-(U7D-A)") (class "Default")
      (node (ref "R19") (pin "2") (pinfunction "2_2") (pintype "passive"))
      (node (ref "U7") (pin "7") (pinfunction "A_7") (pintype "passive"))
    )
    (net (code "156") (name "Net-(U8-RO)") (class "Default")
      (node (ref "R32") (pin "1") (pinfunction "1_1") (pintype "passive"))
      (node (ref "U8") (pin "1") (pinfunction "RO_1") (pintype "output"))
    )
    (net (code "157") (name "Net-(U9A-A)") (class "Default")
      (node (ref "R46") (pin "2") (pinfunction "2_2") (pintype "passive"))
      (node (ref "U9") (pin "1") (pinfunction "A_1") (pintype "passive"))
    )
    (net (code "158") (name "Net-(U9B-A)") (class "Default")
      (node (ref "R47") (pin "2") (pinfunction "2_2") (pintype "passive"))
      (node (ref "U9") (pin "3") (pinfunction "A_3") (pintype "passive"))
    )
    (net (code "159") (name "Net-(U9C-A)") (class "Default")
      (node (ref "R44") (pin "2") (pinfunction "2_2") (pintype "passive"))
      (node (ref "U9") (pin "5") (pinfunction "A_5") (pintype "passive"))
    )
    (net (code "160") (name "Net-(U9D-A)") (class "Default")
      (node (ref "R45") (pin "2") (pinfunction "2_2") (pintype "passive"))
      (node (ref "U9") (pin "7") (pinfunction "A_7") (pintype "passive"))
    )
    (net (code "161") (name "Net-(U11A-A)") (class "Default")
      (node (ref "R37") (pin "2") (pinfunction "2_2") (pintype "passive"))
      (node (ref "U11") (pin "1") (pinfunction "A_1") (pintype "passive"))
    )
    (net (code "162") (name "Net-(U11A-E)") (class "Default")
      (node (ref "R54") (pin "2") (pinfunction "2_2") (pintype "passive"))
      (node (ref "U11") (pin "15") (pinfunction "E_15") (pintype "passive"))
    )
    (net (code "163") (name "Net-(U11B-A)") (class "Default")
      (node (ref "R38") (pin "2") (pinfunction "2_2") (pintype "passive"))
      (node (ref "U11") (pin "3") (pinfunction "A_3") (pintype "passive"))
    )
    (net (code "164") (name "Net-(U11C-A)") (class "Default")
      (node (ref "R39") (pin "1") (pinfunction "1_1") (pintype "passive"))
      (node (ref "U11") (pin "5") (pinfunction "A_5") (pintype "passive"))
    )
    (net (code "165") (name "Net-(U11C-E)") (class "Default")
      (node (ref "R53") (pin "2") (pinfunction "2_2") (pintype "passive"))
      (node (ref "U11") (pin "11") (pinfunction "E_11") (pintype "passive"))
    )
    (net (code "166") (name "Net-(U11D-A)") (class "Default")
      (node (ref "R52") (pin "2") (pinfunction "2_2") (pintype "passive"))
      (node (ref "U11") (pin "7") (pinfunction "A_7") (pintype "passive"))
    )
    (net (code "167") (name "Net-(U13A-A)") (class "Default")
      (node (ref "R74") (pin "1") (pinfunction "1_1") (pintype "passive"))
      (node (ref "U13") (pin "1") (pinfunction "A_1") (pintype "passive"))
    )
    (net (code "168") (name "Net-(U13A-E)") (class "Default")
      (node (ref "R81") (pin "2") (pinfunction "2_2") (pintype "passive"))
      (node (ref "U13") (pin "15") (pinfunction "E_15") (pintype "passive"))
    )
    (net (code "169") (name "Net-(U13B-A)") (class "Default")
      (node (ref "R75") (pin "1") (pinfunction "1_1") (pintype "passive"))
      (node (ref "U13") (pin "3") (pinfunction "A_3") (pintype "passive"))
    )
    (net (code "170") (name "Net-(U13C-A)") (class "Default")
      (node (ref "R76") (pin "1") (pinfunction "1_1") (pintype "passive"))
      (node (ref "U13") (pin "5") (pinfunction "A_5") (pintype "passive"))
    )
    (net (code "171") (name "Net-(U13C-E)") (class "Default")
      (node (ref "R86") (pin "2") (pinfunction "2_2") (pintype "passive"))
      (node (ref "U13") (pin "11") (pinfunction "E_11") (pintype "passive"))
    )
    (net (code "172") (name "Net-(U13D-A)") (class "Default")
      (node (ref "R77") (pin "1") (pinfunction "1_1") (pintype "passive"))
      (node (ref "U13") (pin "7") (pinfunction "A_7") (pintype "passive"))
    )
    (net (code "173") (name "Net-(U14A-A)") (class "Default")
      (node (ref "R89") (pin "2") (pinfunction "2_2") (pintype "passive"))
      (node (ref "U14") (pin "1") (pinfunction "A_1") (pintype "passive"))
    )
    (net (code "174") (name "Net-(U14A-E)") (class "Default")
      (node (ref "R94") (pin "2") (pinfunction "2_2") (pintype "passive"))
      (node (ref "U14") (pin "15") (pinfunction "E_15") (pintype "passive"))
    )
    (net (code "175") (name "Net-(U14B-A)") (class "Default")
      (node (ref "R90") (pin "2") (pinfunction "2_2") (pintype "passive"))
      (node (ref "U14") (pin "3") (pinfunction "A_3") (pintype "passive"))
    )
    (net (code "176") (name "Net-(U14C-A)") (class "Default")
      (node (ref "R123") (pin "1") (pinfunction "1_1") (pintype "passive"))
      (node (ref "U14") (pin "5") (pinfunction "A_5") (pintype "passive"))
    )
    (net (code "177") (name "Net-(U14C-E)") (class "Default")
      (node (ref "R111") (pin "2") (pinfunction "2_2") (pintype "passive"))
      (node (ref "U14") (pin "11") (pinfunction "E_11") (pintype "passive"))
    )
    (net (code "178") (name "Net-(U14D-A)") (class "Default")
      (node (ref "R124") (pin "1") (pinfunction "1_1") (pintype "passive"))
      (node (ref "U14") (pin "7") (pinfunction "A_7") (pintype "passive"))
    )
    (net (code "179") (name "Net-(U15A-A)") (class "Default")
      (node (ref "R91") (pin "2") (pinfunction "2_2") (pintype "passive"))
      (node (ref "U15") (pin "1") (pinfunction "A_1") (pintype "passive"))
    )
    (net (code "180") (name "Net-(U15A-E)") (class "Default")
      (node (ref "R99") (pin "2") (pinfunction "2_2") (pintype "passive"))
      (node (ref "U15") (pin "15") (pinfunction "E_15") (pintype "passive"))
    )
    (net (code "181") (name "Net-(U15B-A)") (class "Default")
      (node (ref "R92") (pin "2") (pinfunction "2_2") (pintype "passive"))
      (node (ref "U15") (pin "3") (pinfunction "A_3") (pintype "passive"))
    )
    (net (code "182") (name "Net-(U15C-A)") (class "Default")
      (node (ref "R125") (pin "2") (pinfunction "2_2") (pintype "passive"))
      (node (ref "U15") (pin "5") (pinfunction "A_5") (pintype "passive"))
    )
    (net (code "183") (name "Net-(U15C-E)") (class "Default")
      (node (ref "R113") (pin "2") (pinfunction "2_2") (pintype "passive"))
      (node (ref "U15") (pin "11") (pinfunction "E_11") (pintype "passive"))
    )
    (net (code "184") (name "Net-(U15D-A)") (class "Default")
      (node (ref "R126") (pin "2") (pinfunction "2_2") (pintype "passive"))
      (node (ref "U15") (pin "7") (pinfunction "A_7") (pintype "passive"))
    )
    (net (code "185") (name "Net-(U16A-A)") (class "Default")
      (node (ref "R67") (pin "2") (pinfunction "2_2") (pintype "passive"))
      (node (ref "U16") (pin "1") (pinfunction "A_1") (pintype "passive"))
    )
    (net (code "186") (name "Net-(U16B-A)") (class "Default")
      (node (ref "R70") (pin "2") (pinfunction "2_2") (pintype "passive"))
      (node (ref "U16") (pin "3") (pinfunction "A_3") (pintype "passive"))
    )
    (net (code "187") (name "Net-(U16C-A)") (class "Default")
      (node (ref "R79") (pin "2") (pinfunction "2_2") (pintype "passive"))
      (node (ref "U16") (pin "5") (pinfunction "A_5") (pintype "passive"))
    )
    (net (code "188") (name "Net-(U16D-A)") (class "Default")
      (node (ref "R64") (pin "2") (pinfunction "2_2") (pintype "passive"))
      (node (ref "U16") (pin "7") (pinfunction "A_7") (pintype "passive"))
    )
    (net (code "189") (name "Net-(U17A-A)") (class "Default")
      (node (ref "R61") (pin "2") (pinfunction "2_2") (pintype "passive"))
      (node (ref "U17") (pin "1") (pinfunction "A_1") (pintype "passive"))
    )
    (net (code "190") (name "Net-(U17B-A)") (class "Default")
      (node (ref "R129") (pin "2") (pinfunction "2_2") (pintype "passive"))
      (node (ref "U17") (pin "3") (pinfunction "A_3") (pintype "passive"))
    )
    (net (code "191") (name "Net-(U17C-A)") (class "Default")
      (node (ref "R130") (pin "2") (pinfunction "2_2") (pintype "passive"))
      (node (ref "U17") (pin "5") (pinfunction "A_5") (pintype "passive"))
    )
    (net (code "192") (name "Net-(U19A-A)") (class "Default")
      (node (ref "R103") (pin "1") (pinfunction "1_1") (pintype "passive"))
      (node (ref "U19") (pin "1") (pinfunction "A_1") (pintype "passive"))
    )
    (net (code "193") (name "Net-(U19A-E)") (class "Default")
      (node (ref "R116") (pin "2") (pinfunction "2_2") (pintype "passive"))
      (node (ref "U19") (pin "15") (pinfunction "E_15") (pintype "passive"))
    )
    (net (code "194") (name "Net-(U19B-A)") (class "Default")
      (node (ref "R104") (pin "1") (pinfunction "1_1") (pintype "passive"))
      (node (ref "U19") (pin "3") (pinfunction "A_3") (pintype "passive"))
    )
    (net (code "195") (name "Net-(U19C-A)") (class "Default")
      (node (ref "R105") (pin "1") (pinfunction "1_1") (pintype "passive"))
      (node (ref "U19") (pin "5") (pinfunction "A_5") (pintype "passive"))
    )
    (net (code "196") (name "Net-(U19C-E)") (class "Default")
      (node (ref "R115") (pin "2") (pinfunction "2_2") (pintype "passive"))
      (node (ref "U19") (pin "11") (pinfunction "E_11") (pintype "passive"))
    )
    (net (code "197") (name "Net-(U19D-A)") (class "Default")
      (node (ref "R106") (pin "1") (pinfunction "1_1") (pintype "passive"))
      (node (ref "U19") (pin "7") (pinfunction "A_7") (pintype "passive"))
    )
    (net (code "198") (name "Net-(W1-C1)") (class "Default")
      (node (ref "R15") (pin "1") (pinfunction "1_1") (pintype "passive"))
      (node (ref "W1") (pin "1") (pinfunction "C1_1") (pintype "passive"))
    )
    (net (code "199") (name "Net-(W2-C1)") (class "Default")
      (node (ref "R36") (pin "1") (pinfunction "1_1") (pintype "passive"))
      (node (ref "W2") (pin "1") (pinfunction "C1_1") (pintype "passive"))
    )
    (net (code "200") (name "unconnected-(P12-Pad8)") (class "Default")
      (node (ref "P12") (pin "8") (pinfunction "8_8") (pintype "passive"))
    )
    (net (code "201") (name "unconnected-(P13-Pad8)") (class "Default")
      (node (ref "P13") (pin "8") (pinfunction "8_8") (pintype "passive"))
    )
    (net (code "202") (name "unconnected-(U1-NC-Pad8)") (class "Default")
      (node (ref "U1") (pin "8") (pinfunction "NC_8") (pintype "passive+no_connect"))
    )
    (net (code "203") (name "unconnected-(U3-R2IN-Pad8)") (class "Default")
      (node (ref "U3") (pin "8") (pinfunction "R2IN_8") (pintype "input+no_connect"))
    )
    (net (code "204") (name "unconnected-(U3-R2OUT-Pad9)") (class "Default")
      (node (ref "U3") (pin "9") (pinfunction "R2OUT_9") (pintype "output+no_connect"))
    )
    (net (code "205") (name "unconnected-(U3-T2IN-Pad10)") (class "Default")
      (node (ref "U3") (pin "10") (pinfunction "T2IN_10") (pintype "input+no_connect"))
    )
    (net (code "206") (name "unconnected-(U3-T2OUT-Pad7)") (class "Default")
      (node (ref "U3") (pin "7") (pinfunction "T2OUT_7") (pintype "output+no_connect"))
    )
    (net (code "207") (name "unconnected-(U4-CTS-Pad3)") (class "Default")
      (node (ref "U4") (pin "3") (pinfunction "CTS_3") (pintype "passive"))
    )
    (net (code "208") (name "unconnected-(U4-NC-Pad1)") (class "Default")
      (node (ref "U4") (pin "1") (pinfunction "NC_1") (pintype "passive"))
    )
    (net (code "209") (name "unconnected-(U4-NC-Pad2)") (class "Default")
      (node (ref "U4") (pin "2") (pinfunction "NC_2") (pintype "passive"))
    )
    (net (code "210") (name "unconnected-(U4-RST-Pad4)") (class "Default")
      (node (ref "U4") (pin "4") (pinfunction "RST_4") (pintype "passive"))
    )
    (net (code "211") (name "unconnected-(U4-RTS-Pad5)") (class "Default")
      (node (ref "U4") (pin "5") (pinfunction "RTS_5") (pintype "passive"))
    )
    (net (code "212") (name "unconnected-(U5-PA11{slash}CANRX{slash}TIM1_CH4-Pad44)") (class "Default")
      (node (ref "U5") (pin "44") (pinfunction "PA11/CANRX/TIM1_CH4_44") (pintype "bidirectional"))
    )
    (net (code "213") (name "unconnected-(U5-PA12{slash}CANTX-Pad45)") (class "Default")
      (node (ref "U5") (pin "45") (pinfunction "PA12/CANTX_45") (pintype "bidirectional"))
    )
    (net (code "214") (name "unconnected-(U5-PA15{slash}JTDI-Pad50)") (class "Default")
      (node (ref "U5") (pin "50") (pinfunction "PA15/JTDI_50") (pintype "bidirectional"))
    )
    (net (code "215") (name "unconnected-(U5-PB2{slash}BOOT1-Pad28)") (class "Default")
      (node (ref "U5") (pin "28") (pinfunction "PB2/BOOT1_28") (pintype "bidirectional"))
    )
    (net (code "216") (name "unconnected-(U5-PC12{slash}U5_TX{slash}SDIO_CK-Pad53)") (class "Default")
      (node (ref "U5") (pin "53") (pinfunction "PC12/U5_TX/SDIO_CK_53") (pintype "bidirectional"))
    )
    (net (code "217") (name "unconnected-(U5-PC13-TAMPER-RTC-Pad2)") (class "Default")
      (node (ref "U5") (pin "2") (pinfunction "PC13-TAMPER-RTC_2") (pintype "bidirectional"))
    )
    (net (code "218") (name "unconnected-(U5-PC14-OSC32_IN-Pad3)") (class "Default")
      (node (ref "U5") (pin "3") (pinfunction "PC14-OSC32_IN_3") (pintype "bidirectional"))
    )
    (net (code "219") (name "unconnected-(U5-PC15-OSC32_OUT-Pad4)") (class "Default")
      (node (ref "U5") (pin "4") (pinfunction "PC15-OSC32_OUT_4") (pintype "bidirectional"))
    )
    (net (code "220") (name "unconnected-(U5-PD2{slash}TIM3_ETR{slash}U5_RX{slash}SDIO_CMD-Pad54)") (class "Default")
      (node (ref "U5") (pin "54") (pinfunction "PD2/TIM3_ETR/U5_RX/SDIO_CMD_54") (pintype "bidirectional"))
    )
    (net (code "221") (name "unconnected-(U17D-A-Pad7)") (class "Default")
      (node (ref "U17") (pin "7") (pinfunction "A_7") (pintype "passive"))
    )
    (net (code "222") (name "unconnected-(U17D-C-Pad10)") (class "Default")
      (node (ref "U17") (pin "10") (pinfunction "C_10") (pintype "passive"))
    )
    (net (code "223") (name "unconnected-(U17D-E-Pad9)") (class "Default")
      (node (ref "U17") (pin "9") (pinfunction "E_9") (pintype "passive"))
    )
    (net (code "224") (name "unconnected-(U17D-K-Pad8)") (class "Default")
      (node (ref "U17") (pin "8") (pinfunction "K_8") (pintype "passive"))
    )
  )
)
